# calendar-decoders.net
KiCad netlist of a schematic drawn in EAGLE
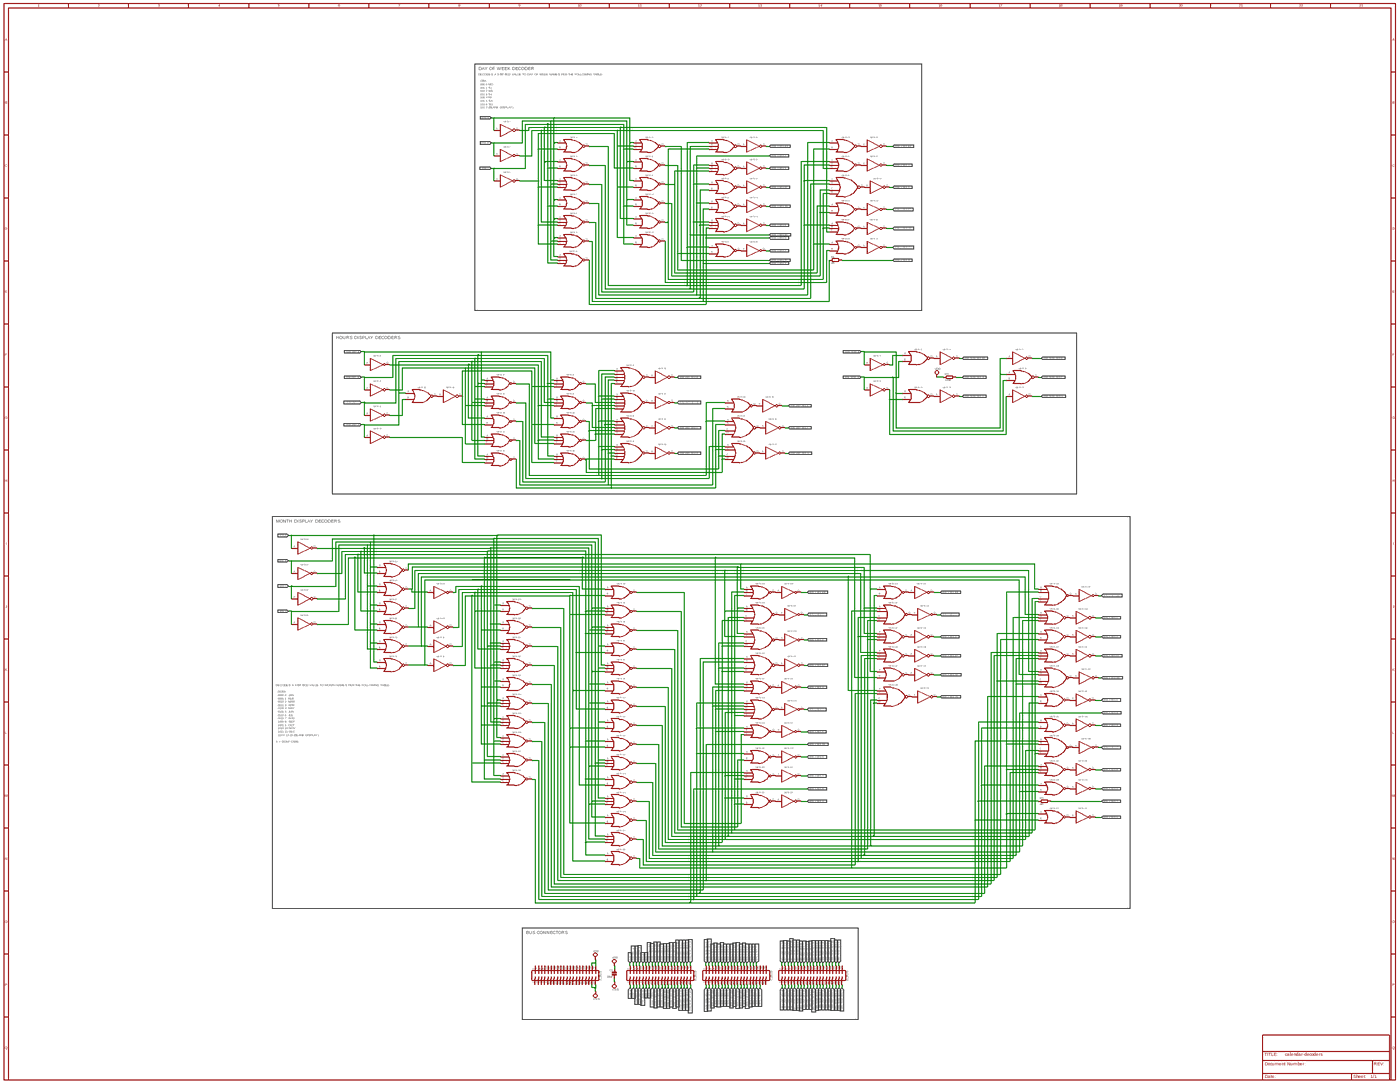
[diagram p0: schematic, sheet 1, overview]
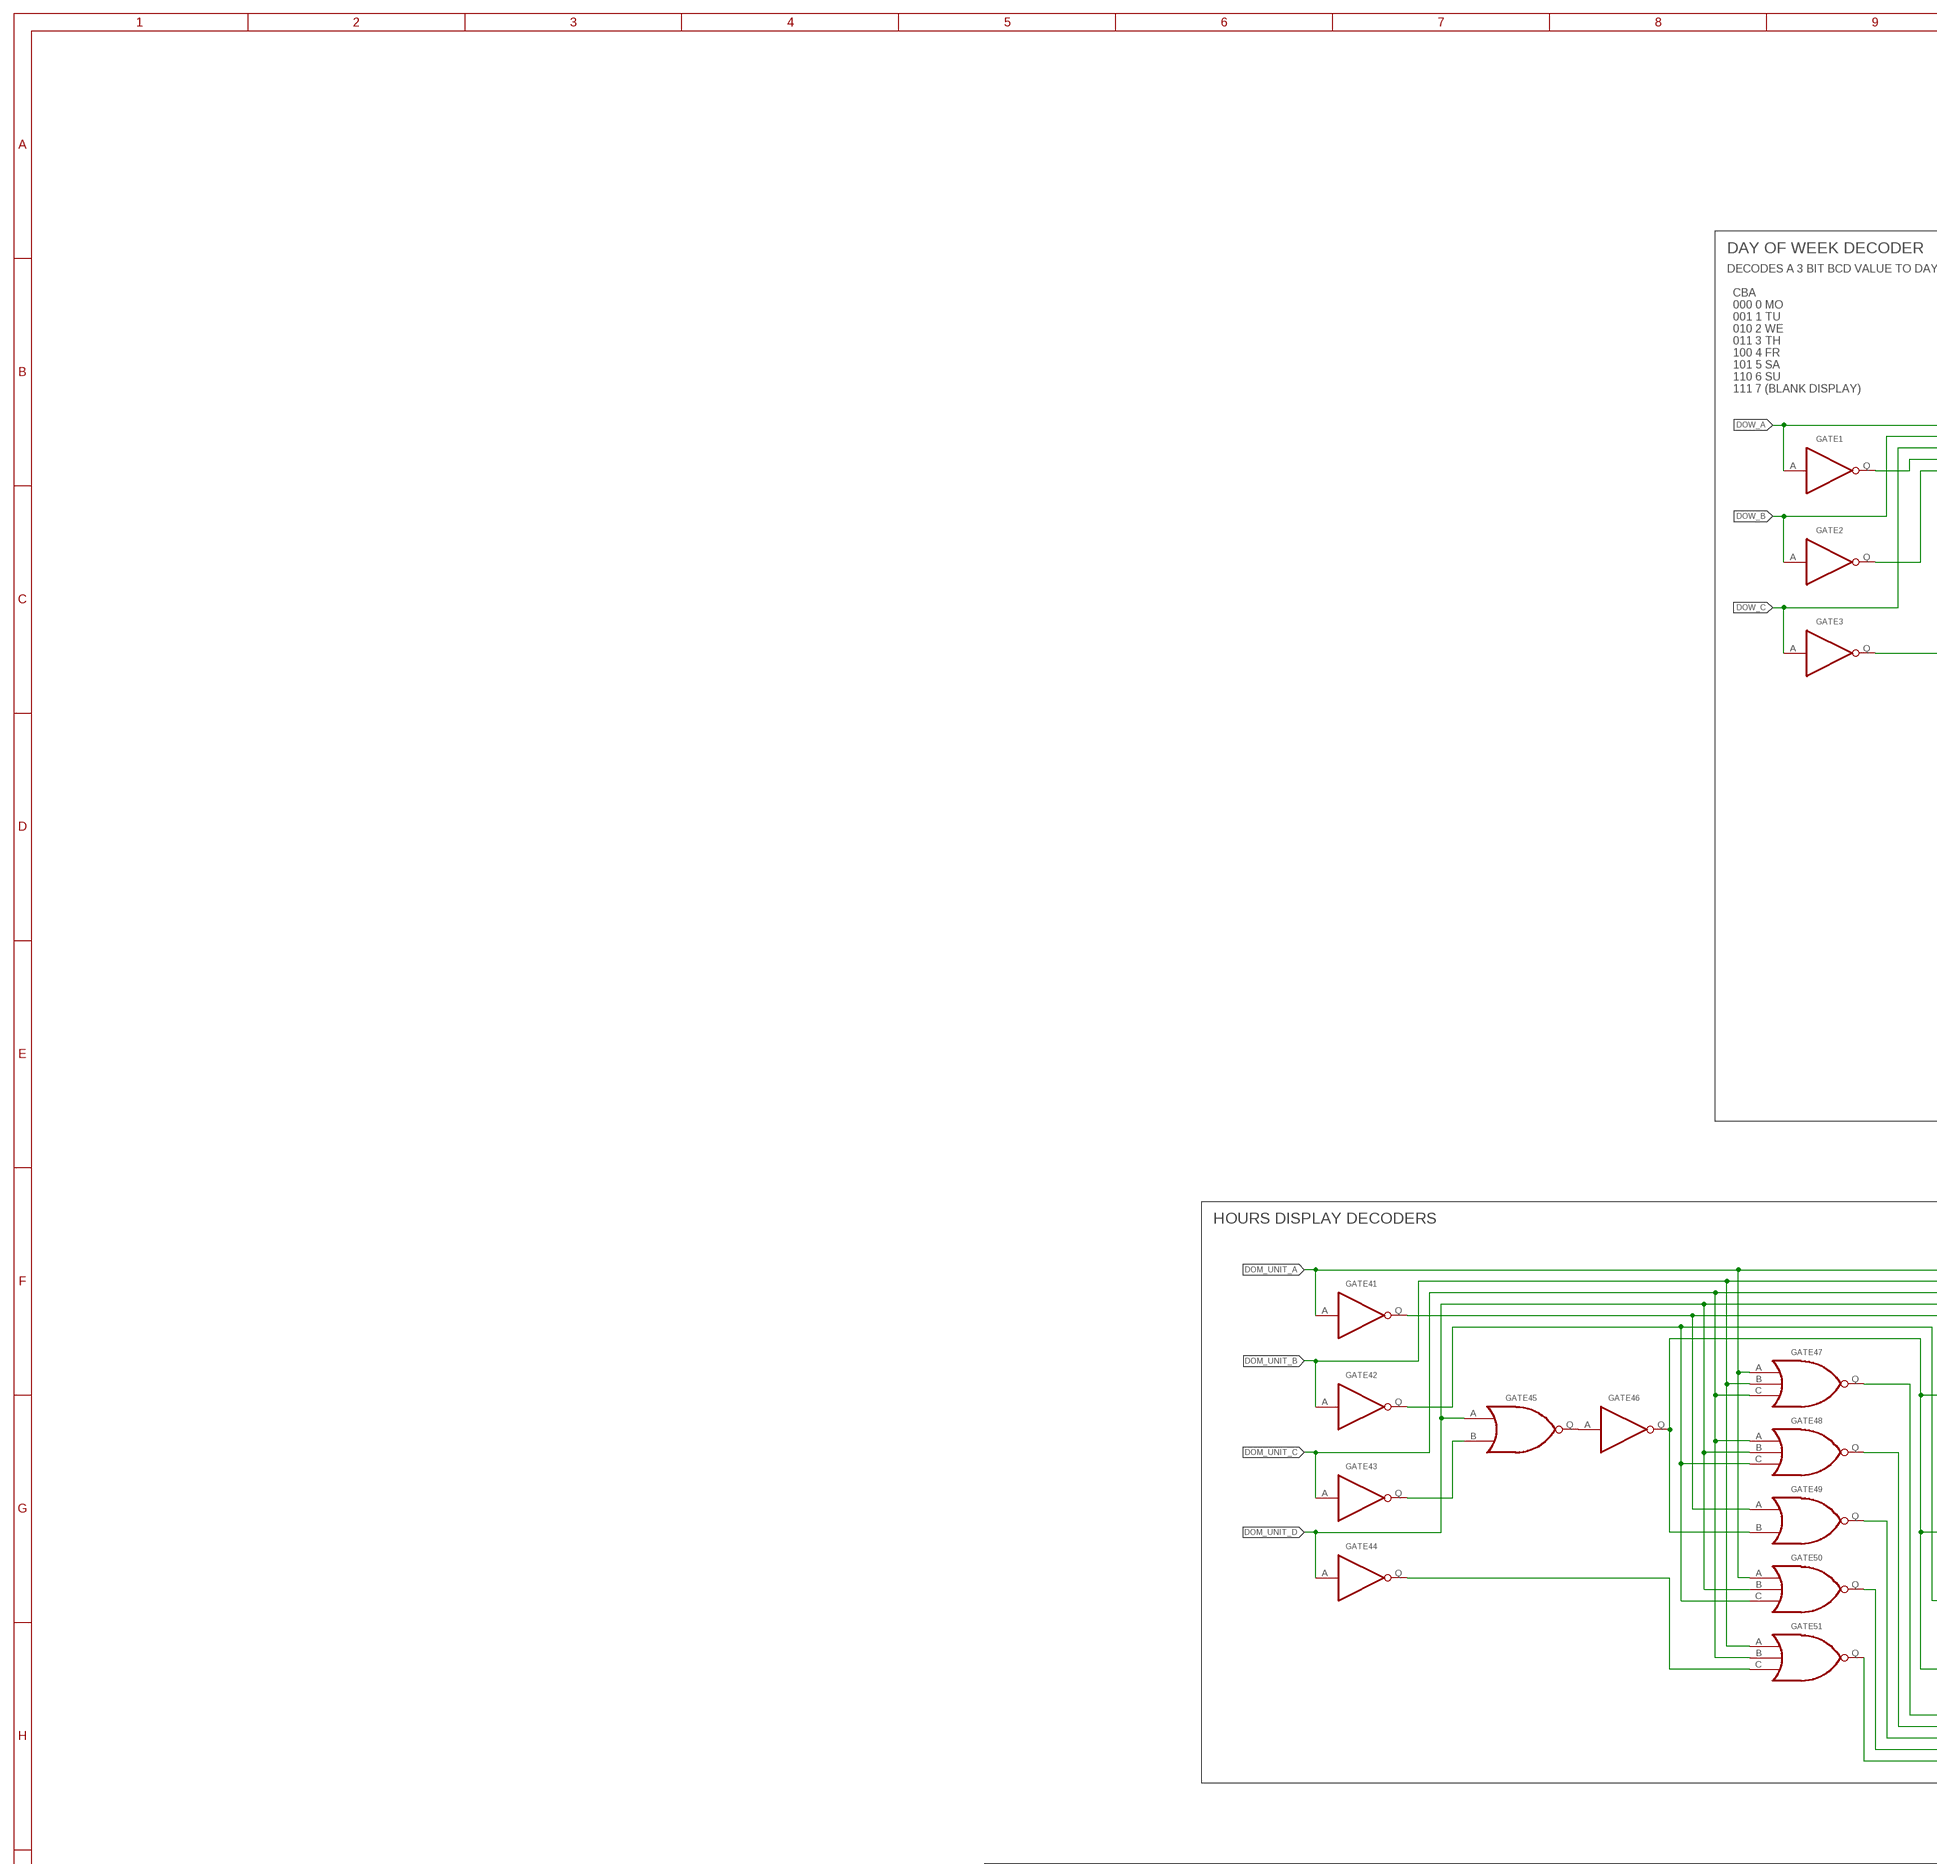
[diagram p1: schematic, sheet 1, part 1 of 6]
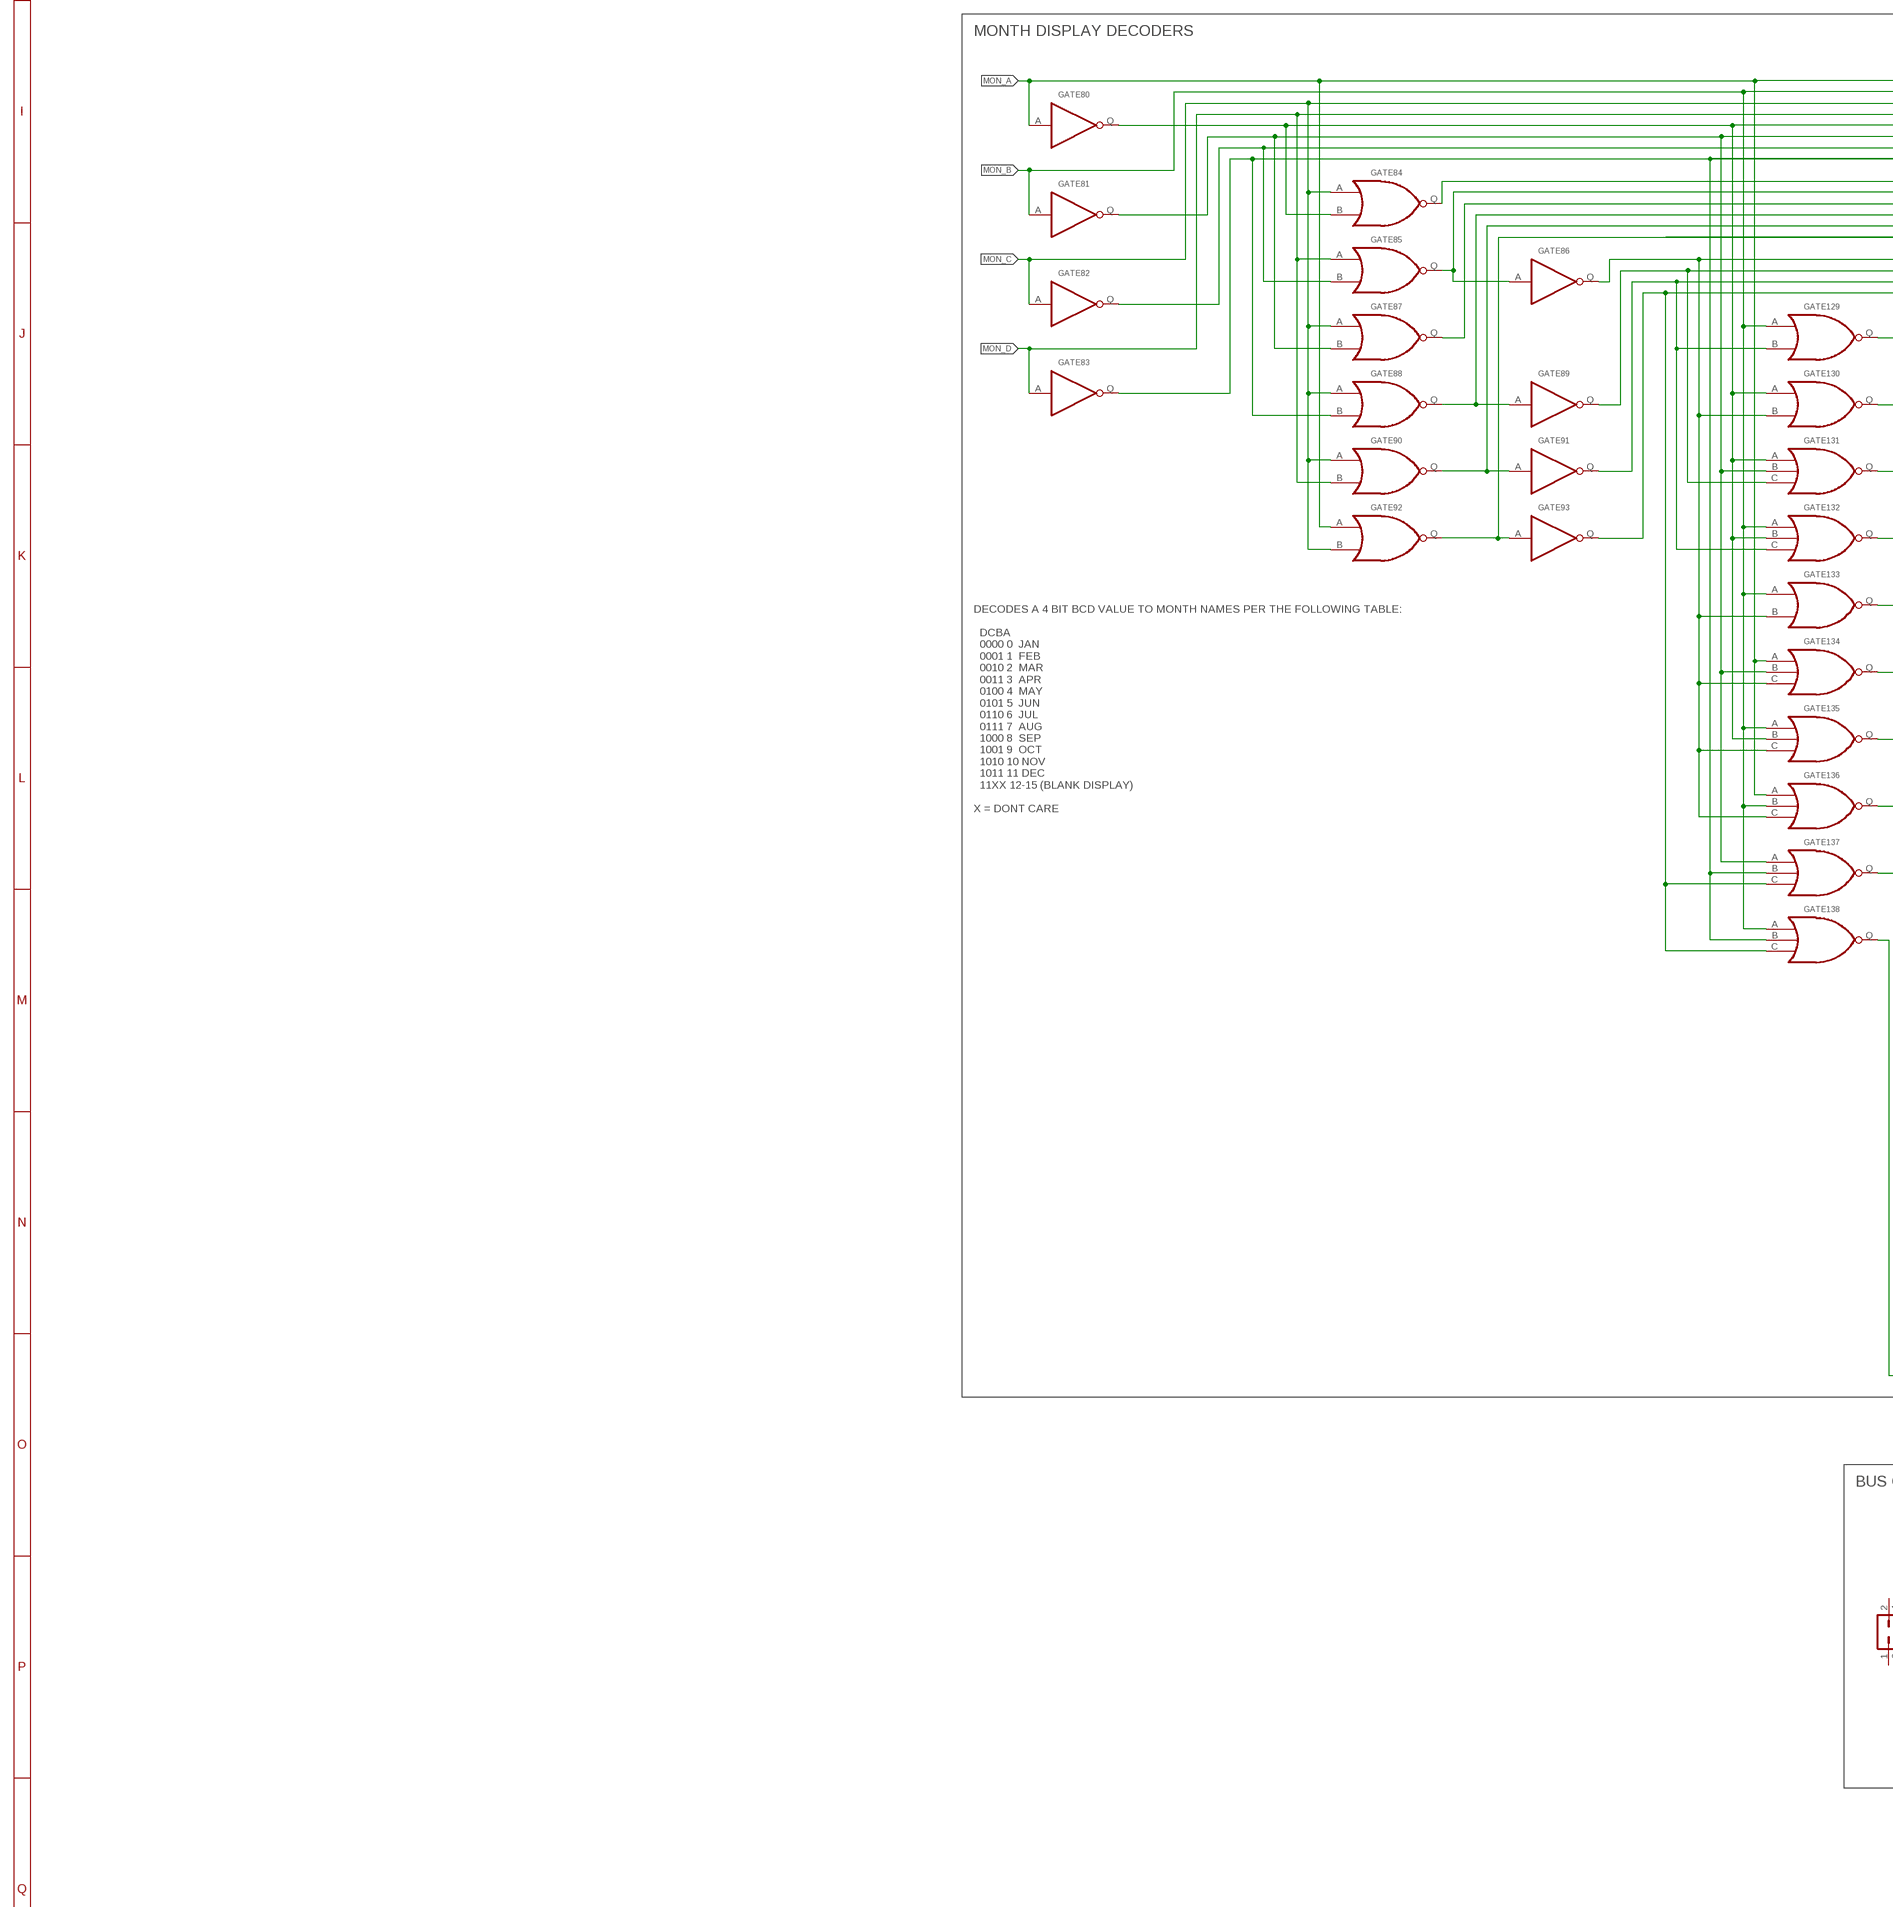
[diagram p2: schematic, sheet 1, part 2 of 6]
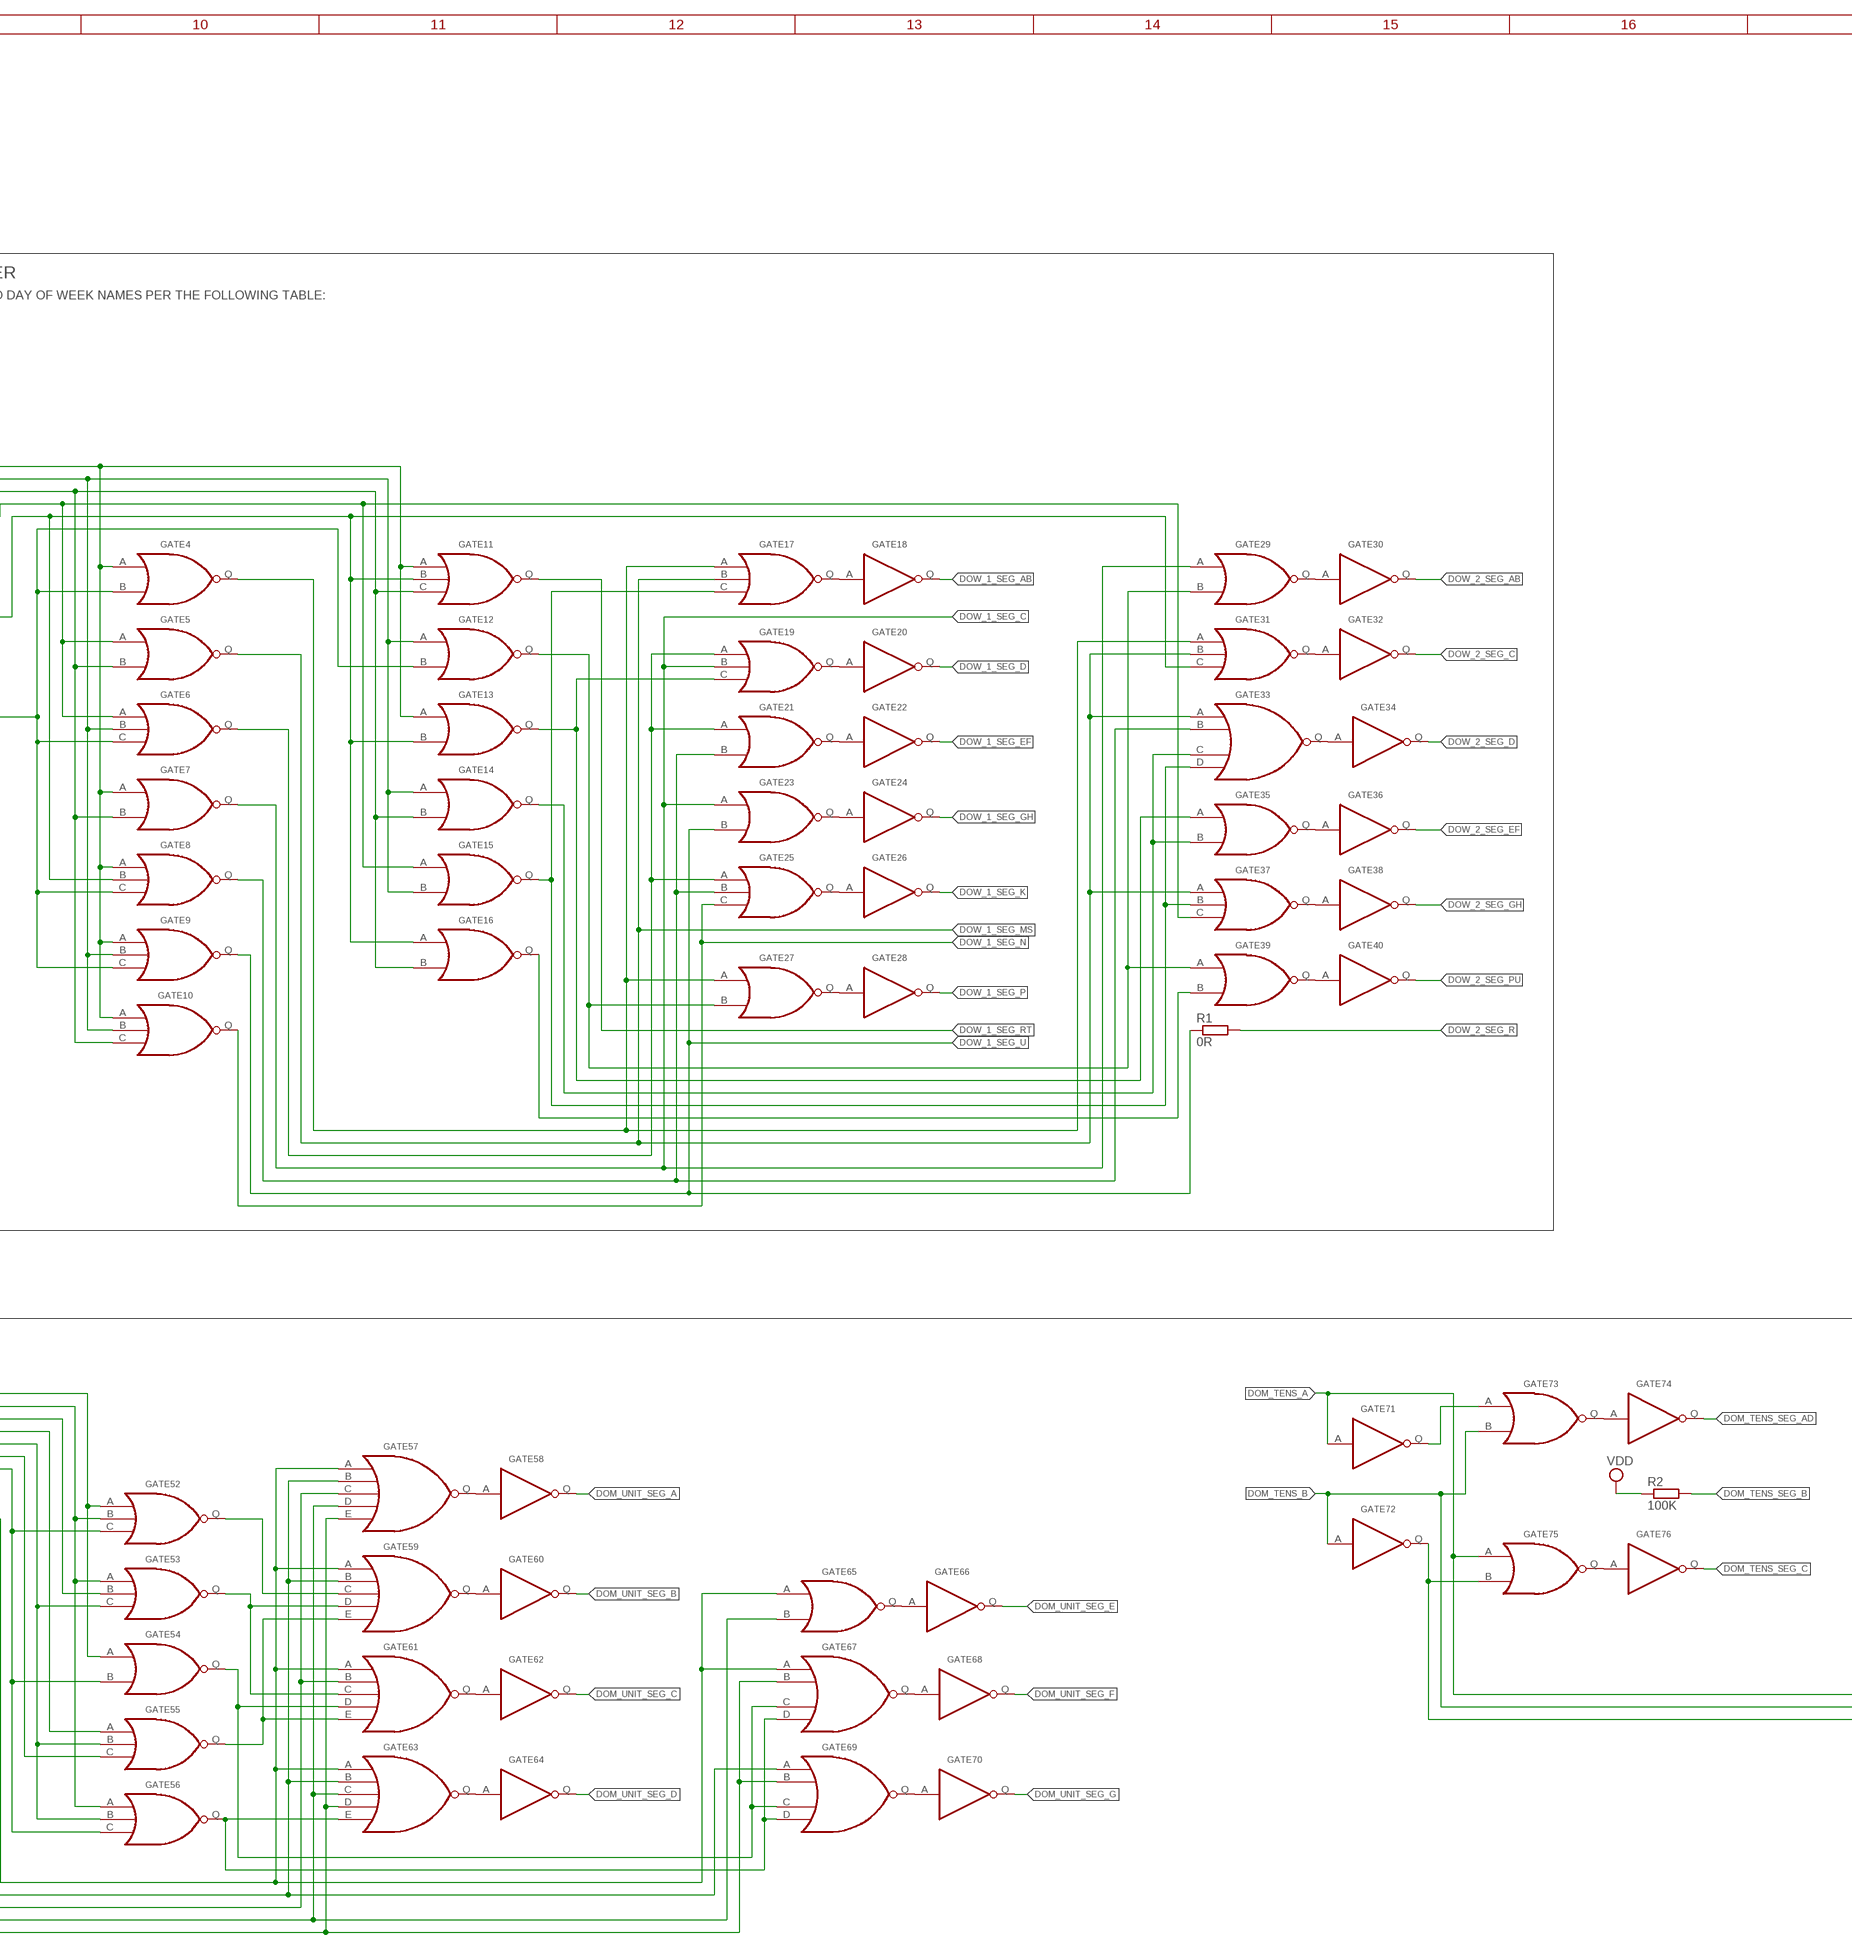
[diagram p3: schematic, sheet 1, part 3 of 6]
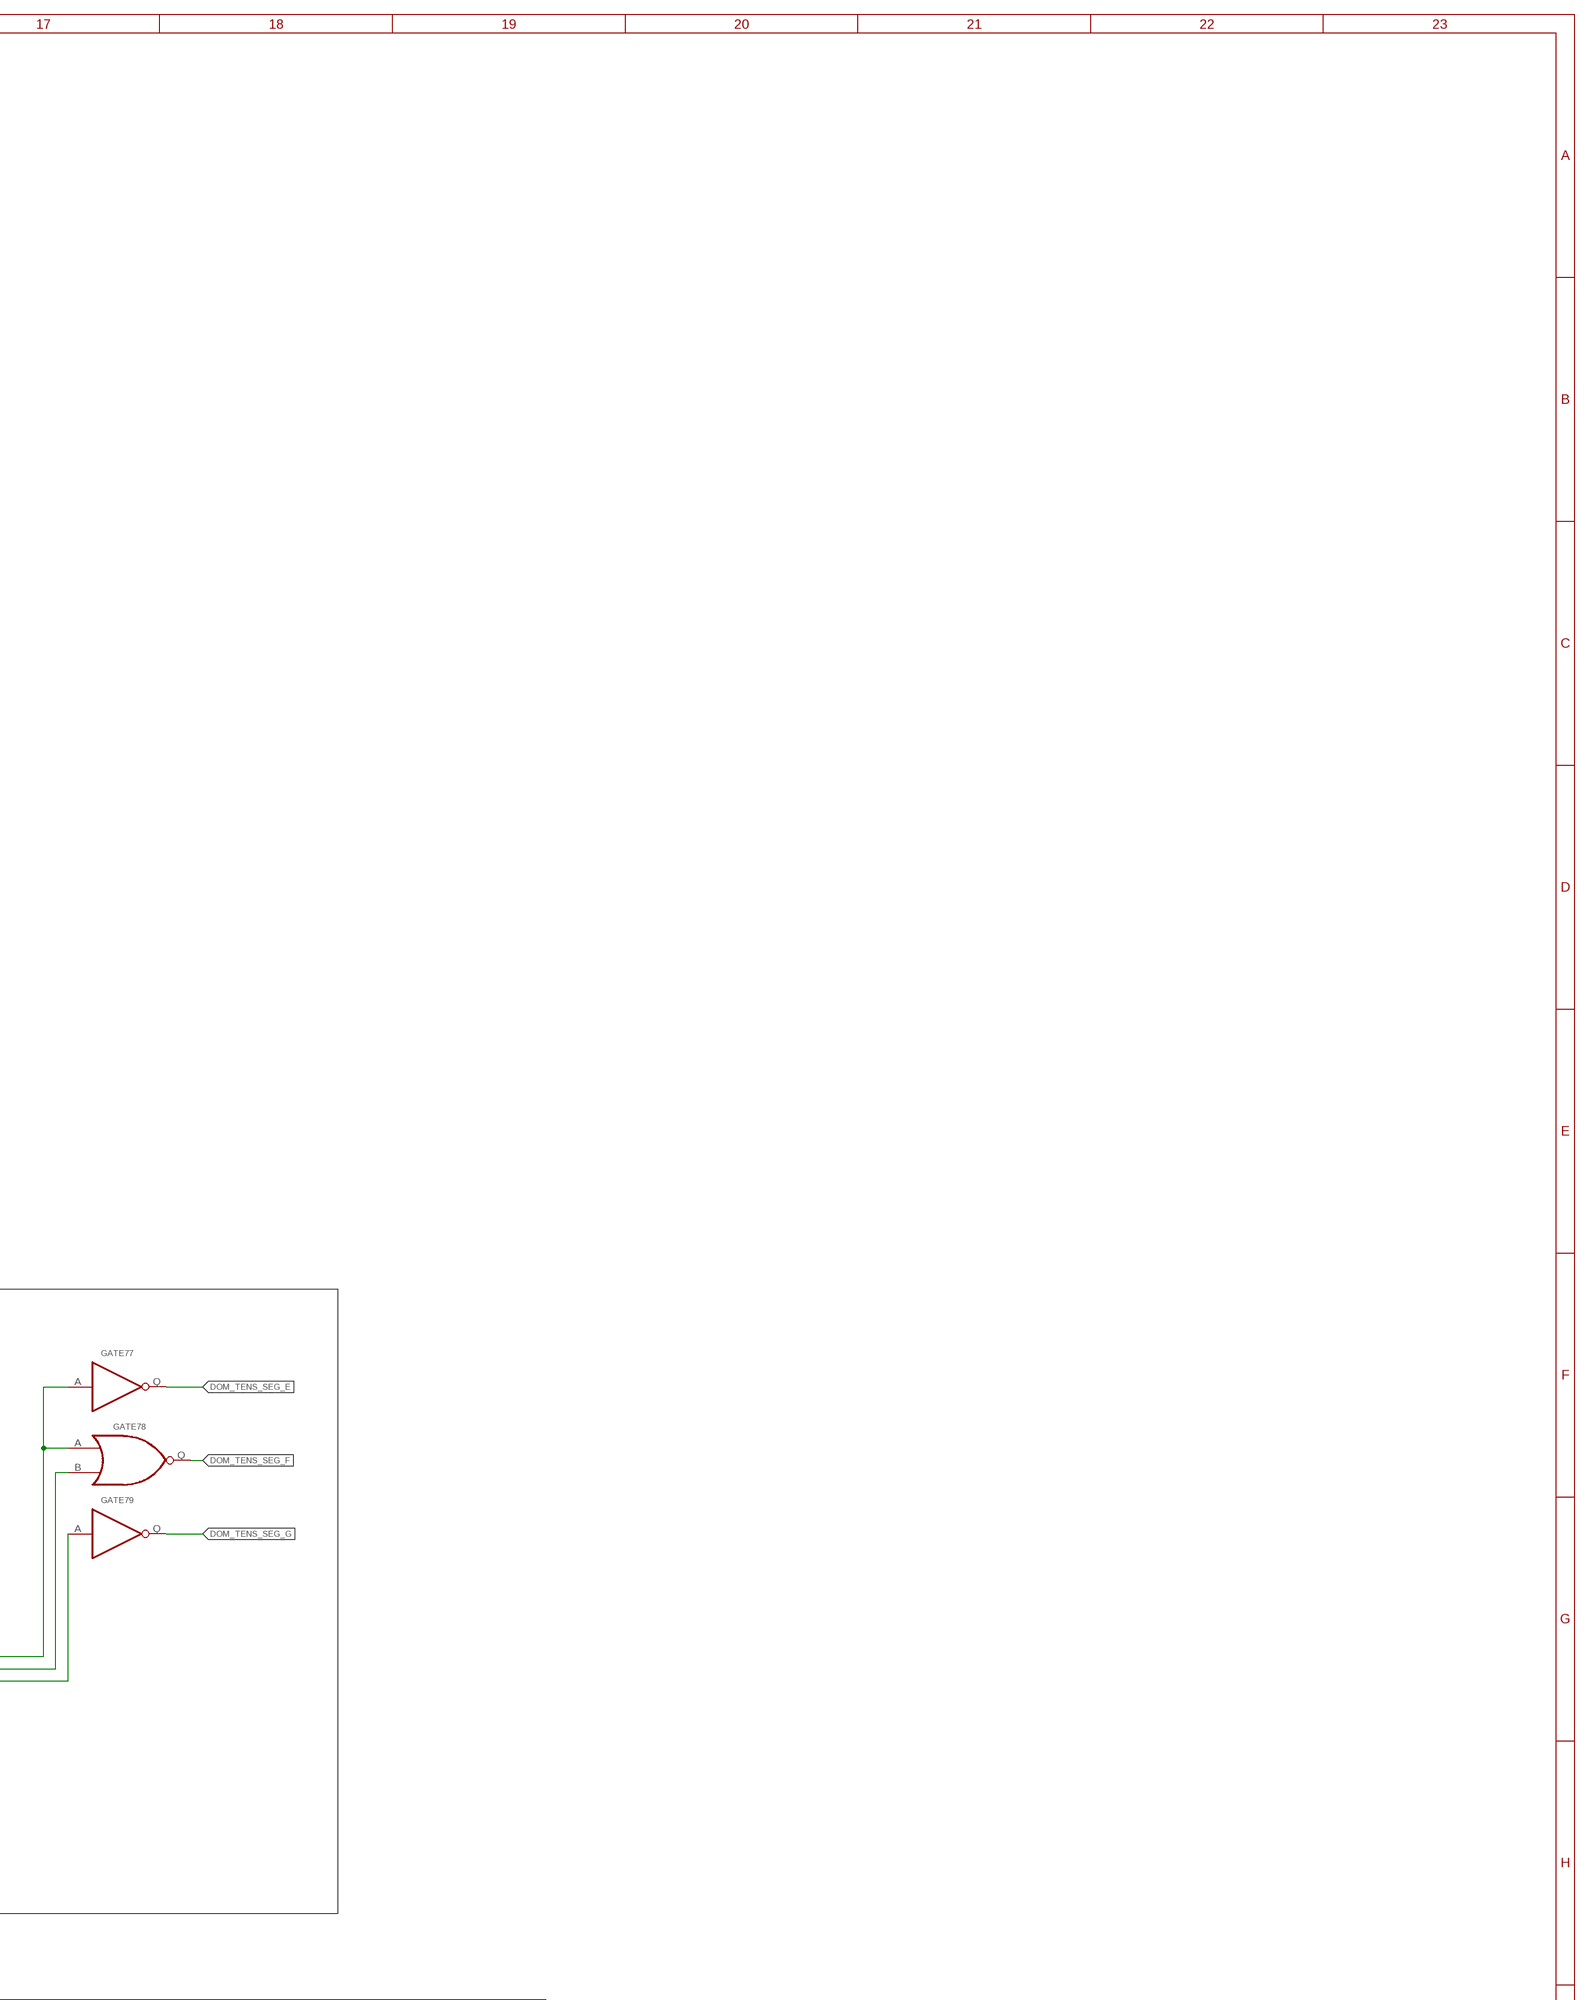
[diagram p4: schematic, sheet 1, part 4 of 6]
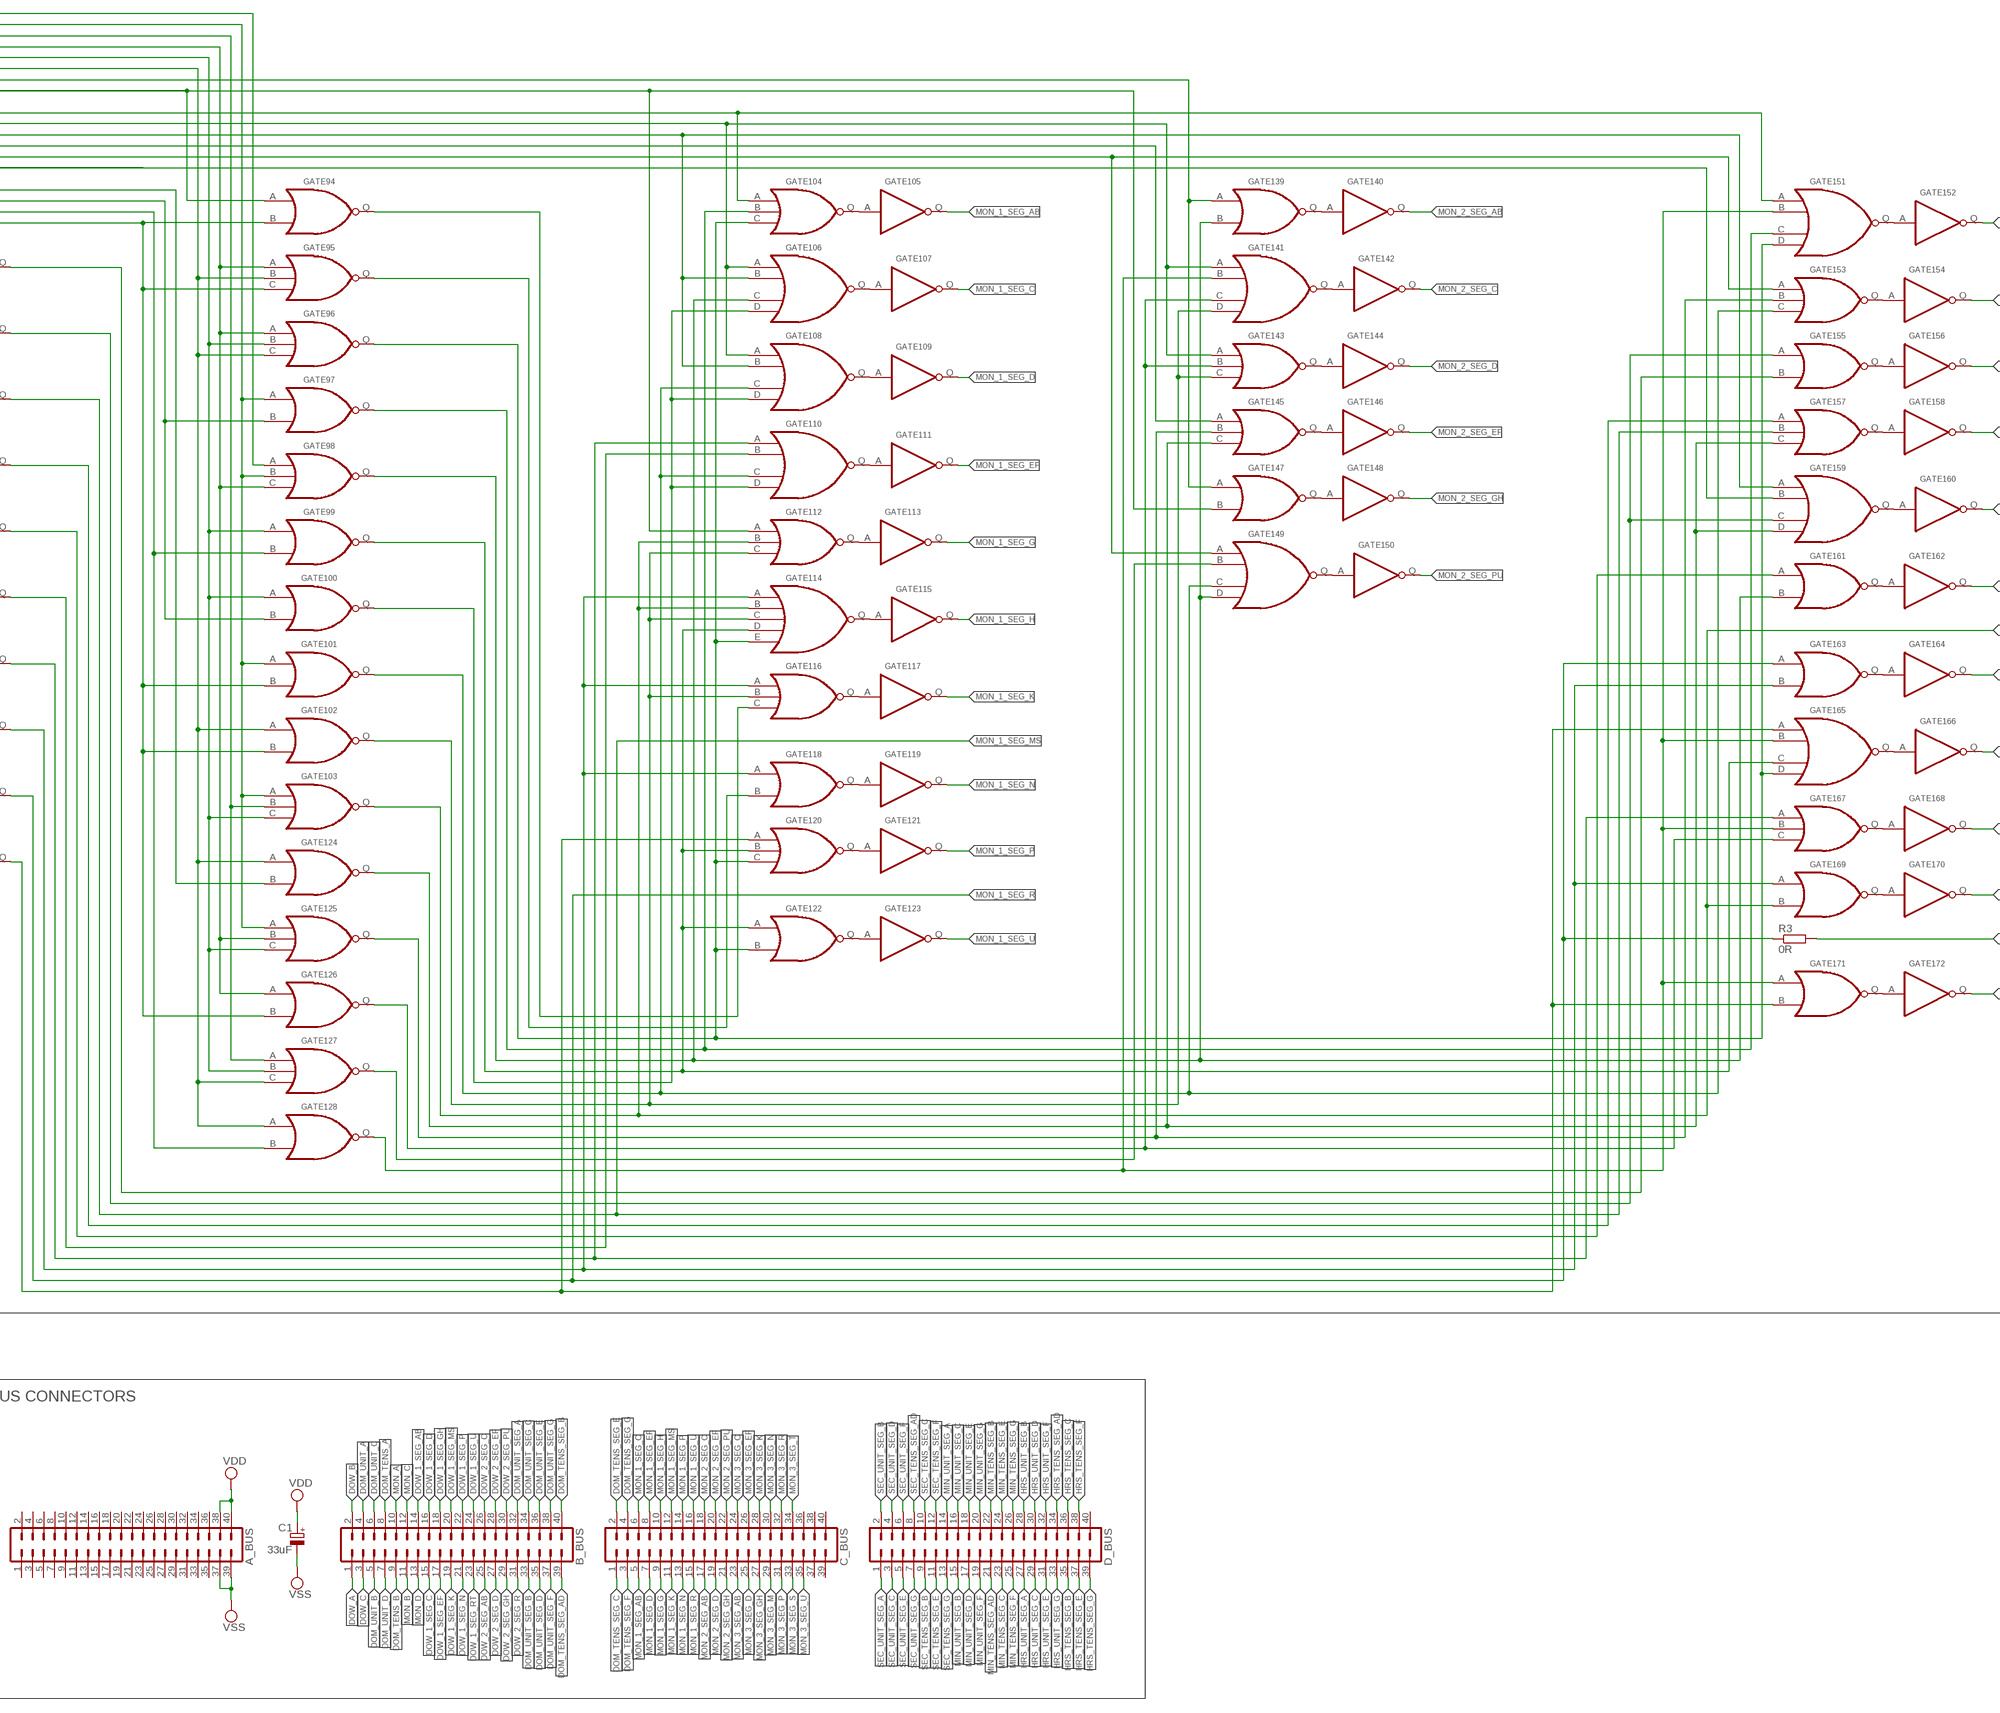
[diagram p5: schematic, sheet 1, part 5 of 6]
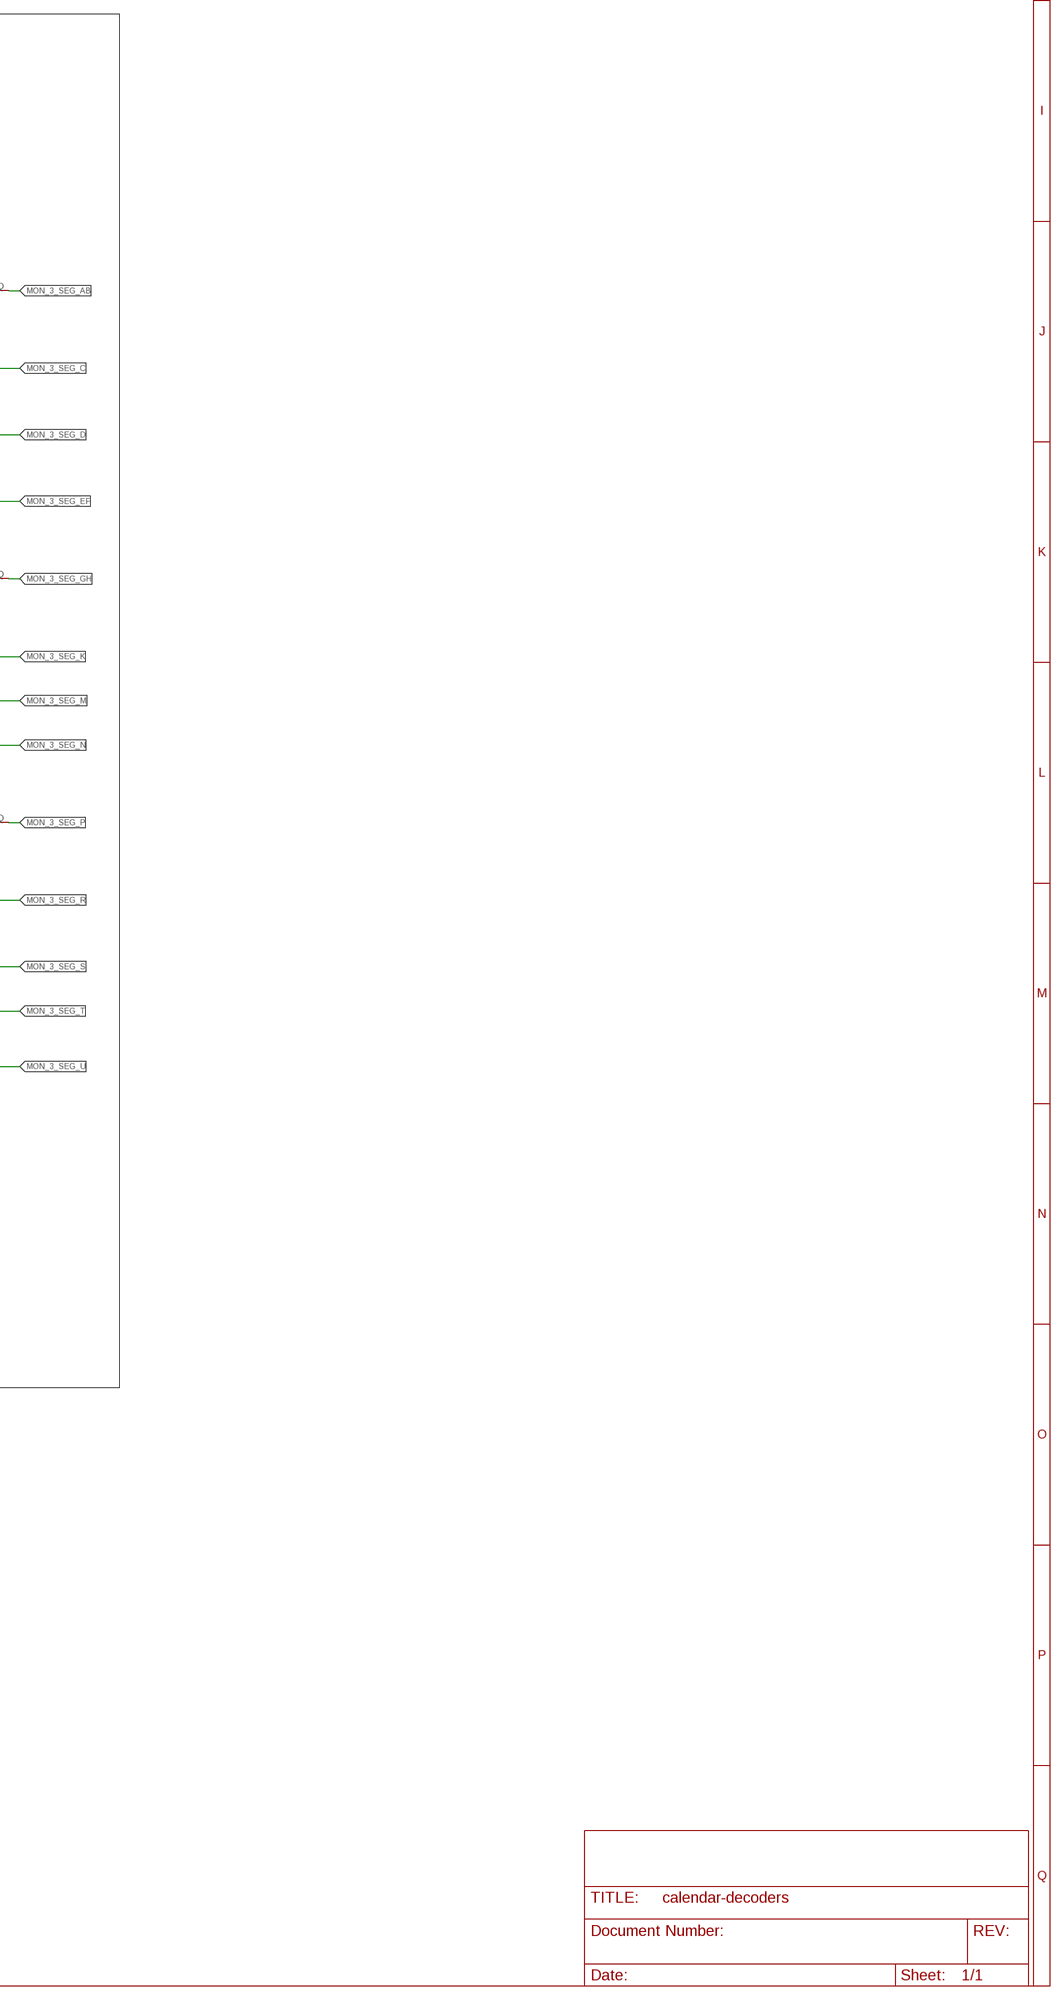
[diagram p6: schematic, sheet 1, part 6 of 6]

(export (version "E")
  (design (tool "Eeschema 10.0.6"))
  (components
    (comp (ref "A_BUS")
      (value "MA20-2")
      (footprint "eagle-import:MA20-2")
      (libsource (lib "eagle-import") (part "MA20-2"))
    )
    (comp (ref "B_BUS")
      (value "MA20-2")
      (footprint "eagle-import:MA20-2")
      (libsource (lib "eagle-import") (part "MA20-2"))
    )
    (comp (ref "C1")
      (value "33uF")
      (footprint "eagle-import:E2,5-6")
      (libsource (lib "eagle-import") (part "CPOL-EUE2.5-6"))
    )
    (comp (ref "C_BUS")
      (value "MA20-2")
      (footprint "eagle-import:MA20-2")
      (libsource (lib "eagle-import") (part "MA20-2"))
    )
    (comp (ref "D_BUS")
      (value "MA20-2")
      (footprint "eagle-import:MA20-2")
      (libsource (lib "eagle-import") (part "MA20-2"))
    )
    (comp (ref "GATE1")
      (value "INVERTER")
      (footprint "eagle-import:INVERTER")
      (libsource (lib "eagle-import") (part "INVERTER"))
    )
    (comp (ref "GATE2")
      (value "INVERTER")
      (footprint "eagle-import:INVERTER")
      (libsource (lib "eagle-import") (part "INVERTER"))
    )
    (comp (ref "GATE3")
      (value "INVERTER")
      (footprint "eagle-import:INVERTER")
      (libsource (lib "eagle-import") (part "INVERTER"))
    )
    (comp (ref "GATE4")
      (value "2NOR")
      (footprint "eagle-import:2NOR")
      (libsource (lib "eagle-import") (part "2NOR"))
    )
    (comp (ref "GATE5")
      (value "2NOR")
      (footprint "eagle-import:2NOR")
      (libsource (lib "eagle-import") (part "2NOR"))
    )
    (comp (ref "GATE6")
      (value "3NOR")
      (footprint "eagle-import:3NOR")
      (libsource (lib "eagle-import") (part "3NOR"))
    )
    (comp (ref "GATE7")
      (value "2NOR")
      (footprint "eagle-import:2NOR")
      (libsource (lib "eagle-import") (part "2NOR"))
    )
    (comp (ref "GATE8")
      (value "3NOR")
      (footprint "eagle-import:3NOR")
      (libsource (lib "eagle-import") (part "3NOR"))
    )
    (comp (ref "GATE9")
      (value "3NOR")
      (footprint "eagle-import:3NOR")
      (libsource (lib "eagle-import") (part "3NOR"))
    )
    (comp (ref "GATE10")
      (value "3NOR")
      (footprint "eagle-import:3NOR")
      (libsource (lib "eagle-import") (part "3NOR"))
    )
    (comp (ref "GATE11")
      (value "3NOR")
      (footprint "eagle-import:3NOR")
      (libsource (lib "eagle-import") (part "3NOR"))
    )
    (comp (ref "GATE12")
      (value "2NOR")
      (footprint "eagle-import:2NOR")
      (libsource (lib "eagle-import") (part "2NOR"))
    )
    (comp (ref "GATE13")
      (value "2NOR")
      (footprint "eagle-import:2NOR")
      (libsource (lib "eagle-import") (part "2NOR"))
    )
    (comp (ref "GATE14")
      (value "2NOR")
      (footprint "eagle-import:2NOR")
      (libsource (lib "eagle-import") (part "2NOR"))
    )
    (comp (ref "GATE15")
      (value "2NOR")
      (footprint "eagle-import:2NOR")
      (libsource (lib "eagle-import") (part "2NOR"))
    )
    (comp (ref "GATE16")
      (value "2NOR")
      (footprint "eagle-import:2NOR")
      (libsource (lib "eagle-import") (part "2NOR"))
    )
    (comp (ref "GATE17")
      (value "3NOR")
      (footprint "eagle-import:3NOR")
      (libsource (lib "eagle-import") (part "3NOR"))
    )
    (comp (ref "GATE18")
      (value "INVERTER")
      (footprint "eagle-import:INVERTER")
      (libsource (lib "eagle-import") (part "INVERTER"))
    )
    (comp (ref "GATE19")
      (value "3NOR")
      (footprint "eagle-import:3NOR")
      (libsource (lib "eagle-import") (part "3NOR"))
    )
    (comp (ref "GATE20")
      (value "INVERTER")
      (footprint "eagle-import:INVERTER")
      (libsource (lib "eagle-import") (part "INVERTER"))
    )
    (comp (ref "GATE21")
      (value "2NOR")
      (footprint "eagle-import:2NOR")
      (libsource (lib "eagle-import") (part "2NOR"))
    )
    (comp (ref "GATE22")
      (value "INVERTER")
      (footprint "eagle-import:INVERTER")
      (libsource (lib "eagle-import") (part "INVERTER"))
    )
    (comp (ref "GATE23")
      (value "2NOR")
      (footprint "eagle-import:2NOR")
      (libsource (lib "eagle-import") (part "2NOR"))
    )
    (comp (ref "GATE24")
      (value "INVERTER")
      (footprint "eagle-import:INVERTER")
      (libsource (lib "eagle-import") (part "INVERTER"))
    )
    (comp (ref "GATE25")
      (value "3NOR")
      (footprint "eagle-import:3NOR")
      (libsource (lib "eagle-import") (part "3NOR"))
    )
    (comp (ref "GATE26")
      (value "INVERTER")
      (footprint "eagle-import:INVERTER")
      (libsource (lib "eagle-import") (part "INVERTER"))
    )
    (comp (ref "GATE27")
      (value "2NOR")
      (footprint "eagle-import:2NOR")
      (libsource (lib "eagle-import") (part "2NOR"))
    )
    (comp (ref "GATE28")
      (value "INVERTER")
      (footprint "eagle-import:INVERTER")
      (libsource (lib "eagle-import") (part "INVERTER"))
    )
    (comp (ref "GATE29")
      (value "2NOR")
      (footprint "eagle-import:2NOR")
      (libsource (lib "eagle-import") (part "2NOR"))
    )
    (comp (ref "GATE30")
      (value "INVERTER")
      (footprint "eagle-import:INVERTER")
      (libsource (lib "eagle-import") (part "INVERTER"))
    )
    (comp (ref "GATE31")
      (value "3NOR")
      (footprint "eagle-import:3NOR")
      (libsource (lib "eagle-import") (part "3NOR"))
    )
    (comp (ref "GATE32")
      (value "INVERTER")
      (footprint "eagle-import:INVERTER")
      (libsource (lib "eagle-import") (part "INVERTER"))
    )
    (comp (ref "GATE33")
      (value "4NOR")
      (footprint "eagle-import:4NOR")
      (libsource (lib "eagle-import") (part "4NOR"))
    )
    (comp (ref "GATE34")
      (value "INVERTER")
      (footprint "eagle-import:INVERTER")
      (libsource (lib "eagle-import") (part "INVERTER"))
    )
    (comp (ref "GATE35")
      (value "2NOR")
      (footprint "eagle-import:2NOR")
      (libsource (lib "eagle-import") (part "2NOR"))
    )
    (comp (ref "GATE36")
      (value "INVERTER")
      (footprint "eagle-import:INVERTER")
      (libsource (lib "eagle-import") (part "INVERTER"))
    )
    (comp (ref "GATE37")
      (value "3NOR")
      (footprint "eagle-import:3NOR")
      (libsource (lib "eagle-import") (part "3NOR"))
    )
    (comp (ref "GATE38")
      (value "INVERTER")
      (footprint "eagle-import:INVERTER")
      (libsource (lib "eagle-import") (part "INVERTER"))
    )
    (comp (ref "GATE39")
      (value "2NOR")
      (footprint "eagle-import:2NOR")
      (libsource (lib "eagle-import") (part "2NOR"))
    )
    (comp (ref "GATE40")
      (value "INVERTER")
      (footprint "eagle-import:INVERTER")
      (libsource (lib "eagle-import") (part "INVERTER"))
    )
    (comp (ref "GATE41")
      (value "INVERTER")
      (footprint "eagle-import:INVERTER")
      (libsource (lib "eagle-import") (part "INVERTER"))
    )
    (comp (ref "GATE42")
      (value "INVERTER")
      (footprint "eagle-import:INVERTER")
      (libsource (lib "eagle-import") (part "INVERTER"))
    )
    (comp (ref "GATE43")
      (value "INVERTER")
      (footprint "eagle-import:INVERTER")
      (libsource (lib "eagle-import") (part "INVERTER"))
    )
    (comp (ref "GATE44")
      (value "INVERTER")
      (footprint "eagle-import:INVERTER")
      (libsource (lib "eagle-import") (part "INVERTER"))
    )
    (comp (ref "GATE45")
      (value "2NOR")
      (footprint "eagle-import:2NOR")
      (libsource (lib "eagle-import") (part "2NOR"))
    )
    (comp (ref "GATE46")
      (value "INVERTER")
      (footprint "eagle-import:INVERTER")
      (libsource (lib "eagle-import") (part "INVERTER"))
    )
    (comp (ref "GATE47")
      (value "3NOR")
      (footprint "eagle-import:3NOR")
      (libsource (lib "eagle-import") (part "3NOR"))
    )
    (comp (ref "GATE48")
      (value "3NOR")
      (footprint "eagle-import:3NOR")
      (libsource (lib "eagle-import") (part "3NOR"))
    )
    (comp (ref "GATE49")
      (value "2NOR")
      (footprint "eagle-import:2NOR")
      (libsource (lib "eagle-import") (part "2NOR"))
    )
    (comp (ref "GATE50")
      (value "3NOR")
      (footprint "eagle-import:3NOR")
      (libsource (lib "eagle-import") (part "3NOR"))
    )
    (comp (ref "GATE51")
      (value "3NOR")
      (footprint "eagle-import:3NOR")
      (libsource (lib "eagle-import") (part "3NOR"))
    )
    (comp (ref "GATE52")
      (value "3NOR")
      (footprint "eagle-import:3NOR")
      (libsource (lib "eagle-import") (part "3NOR"))
    )
    (comp (ref "GATE53")
      (value "3NOR")
      (footprint "eagle-import:3NOR")
      (libsource (lib "eagle-import") (part "3NOR"))
    )
    (comp (ref "GATE54")
      (value "2NOR")
      (footprint "eagle-import:2NOR")
      (libsource (lib "eagle-import") (part "2NOR"))
    )
    (comp (ref "GATE55")
      (value "3NOR")
      (footprint "eagle-import:3NOR")
      (libsource (lib "eagle-import") (part "3NOR"))
    )
    (comp (ref "GATE56")
      (value "3NOR")
      (footprint "eagle-import:3NOR")
      (libsource (lib "eagle-import") (part "3NOR"))
    )
    (comp (ref "GATE57")
      (value "5NOR")
      (footprint "eagle-import:5NOR")
      (libsource (lib "eagle-import") (part "5NOR"))
    )
    (comp (ref "GATE58")
      (value "INVERTER")
      (footprint "eagle-import:INVERTER")
      (libsource (lib "eagle-import") (part "INVERTER"))
    )
    (comp (ref "GATE59")
      (value "5NOR")
      (footprint "eagle-import:5NOR")
      (libsource (lib "eagle-import") (part "5NOR"))
    )
    (comp (ref "GATE60")
      (value "INVERTER")
      (footprint "eagle-import:INVERTER")
      (libsource (lib "eagle-import") (part "INVERTER"))
    )
    (comp (ref "GATE61")
      (value "5NOR")
      (footprint "eagle-import:5NOR")
      (libsource (lib "eagle-import") (part "5NOR"))
    )
    (comp (ref "GATE62")
      (value "INVERTER")
      (footprint "eagle-import:INVERTER")
      (libsource (lib "eagle-import") (part "INVERTER"))
    )
    (comp (ref "GATE63")
      (value "5NOR")
      (footprint "eagle-import:5NOR")
      (libsource (lib "eagle-import") (part "5NOR"))
    )
    (comp (ref "GATE64")
      (value "INVERTER")
      (footprint "eagle-import:INVERTER")
      (libsource (lib "eagle-import") (part "INVERTER"))
    )
    (comp (ref "GATE65")
      (value "2NOR")
      (footprint "eagle-import:2NOR")
      (libsource (lib "eagle-import") (part "2NOR"))
    )
    (comp (ref "GATE66")
      (value "INVERTER")
      (footprint "eagle-import:INVERTER")
      (libsource (lib "eagle-import") (part "INVERTER"))
    )
    (comp (ref "GATE67")
      (value "4NOR")
      (footprint "eagle-import:4NOR")
      (libsource (lib "eagle-import") (part "4NOR"))
    )
    (comp (ref "GATE68")
      (value "INVERTER")
      (footprint "eagle-import:INVERTER")
      (libsource (lib "eagle-import") (part "INVERTER"))
    )
    (comp (ref "GATE69")
      (value "4NOR")
      (footprint "eagle-import:4NOR")
      (libsource (lib "eagle-import") (part "4NOR"))
    )
    (comp (ref "GATE70")
      (value "INVERTER")
      (footprint "eagle-import:INVERTER")
      (libsource (lib "eagle-import") (part "INVERTER"))
    )
    (comp (ref "GATE71")
      (value "INVERTER")
      (footprint "eagle-import:INVERTER")
      (libsource (lib "eagle-import") (part "INVERTER"))
    )
    (comp (ref "GATE72")
      (value "INVERTER")
      (footprint "eagle-import:INVERTER")
      (libsource (lib "eagle-import") (part "INVERTER"))
    )
    (comp (ref "GATE73")
      (value "2NOR")
      (footprint "eagle-import:2NOR")
      (libsource (lib "eagle-import") (part "2NOR"))
    )
    (comp (ref "GATE74")
      (value "INVERTER")
      (footprint "eagle-import:INVERTER")
      (libsource (lib "eagle-import") (part "INVERTER"))
    )
    (comp (ref "GATE75")
      (value "2NOR")
      (footprint "eagle-import:2NOR")
      (libsource (lib "eagle-import") (part "2NOR"))
    )
    (comp (ref "GATE76")
      (value "INVERTER")
      (footprint "eagle-import:INVERTER")
      (libsource (lib "eagle-import") (part "INVERTER"))
    )
    (comp (ref "GATE77")
      (value "INVERTER")
      (footprint "eagle-import:INVERTER")
      (libsource (lib "eagle-import") (part "INVERTER"))
    )
    (comp (ref "GATE78")
      (value "2NOR")
      (footprint "eagle-import:2NOR")
      (libsource (lib "eagle-import") (part "2NOR"))
    )
    (comp (ref "GATE79")
      (value "INVERTER")
      (footprint "eagle-import:INVERTER")
      (libsource (lib "eagle-import") (part "INVERTER"))
    )
    (comp (ref "GATE80")
      (value "INVERTER")
      (footprint "eagle-import:INVERTER")
      (libsource (lib "eagle-import") (part "INVERTER"))
    )
    (comp (ref "GATE81")
      (value "INVERTER")
      (footprint "eagle-import:INVERTER")
      (libsource (lib "eagle-import") (part "INVERTER"))
    )
    (comp (ref "GATE82")
      (value "INVERTER")
      (footprint "eagle-import:INVERTER")
      (libsource (lib "eagle-import") (part "INVERTER"))
    )
    (comp (ref "GATE83")
      (value "INVERTER")
      (footprint "eagle-import:INVERTER")
      (libsource (lib "eagle-import") (part "INVERTER"))
    )
    (comp (ref "GATE84")
      (value "2NOR")
      (footprint "eagle-import:2NOR")
      (libsource (lib "eagle-import") (part "2NOR"))
    )
    (comp (ref "GATE85")
      (value "2NOR")
      (footprint "eagle-import:2NOR")
      (libsource (lib "eagle-import") (part "2NOR"))
    )
    (comp (ref "GATE86")
      (value "INVERTER")
      (footprint "eagle-import:INVERTER")
      (libsource (lib "eagle-import") (part "INVERTER"))
    )
    (comp (ref "GATE87")
      (value "2NOR")
      (footprint "eagle-import:2NOR")
      (libsource (lib "eagle-import") (part "2NOR"))
    )
    (comp (ref "GATE88")
      (value "2NOR")
      (footprint "eagle-import:2NOR")
      (libsource (lib "eagle-import") (part "2NOR"))
    )
    (comp (ref "GATE89")
      (value "INVERTER")
      (footprint "eagle-import:INVERTER")
      (libsource (lib "eagle-import") (part "INVERTER"))
    )
    (comp (ref "GATE90")
      (value "2NOR")
      (footprint "eagle-import:2NOR")
      (libsource (lib "eagle-import") (part "2NOR"))
    )
    (comp (ref "GATE91")
      (value "INVERTER")
      (footprint "eagle-import:INVERTER")
      (libsource (lib "eagle-import") (part "INVERTER"))
    )
    (comp (ref "GATE92")
      (value "2NOR")
      (footprint "eagle-import:2NOR")
      (libsource (lib "eagle-import") (part "2NOR"))
    )
    (comp (ref "GATE93")
      (value "INVERTER")
      (footprint "eagle-import:INVERTER")
      (libsource (lib "eagle-import") (part "INVERTER"))
    )
    (comp (ref "GATE94")
      (value "2NOR")
      (footprint "eagle-import:2NOR")
      (libsource (lib "eagle-import") (part "2NOR"))
    )
    (comp (ref "GATE95")
      (value "3NOR")
      (footprint "eagle-import:3NOR")
      (libsource (lib "eagle-import") (part "3NOR"))
    )
    (comp (ref "GATE96")
      (value "3NOR")
      (footprint "eagle-import:3NOR")
      (libsource (lib "eagle-import") (part "3NOR"))
    )
    (comp (ref "GATE97")
      (value "2NOR")
      (footprint "eagle-import:2NOR")
      (libsource (lib "eagle-import") (part "2NOR"))
    )
    (comp (ref "GATE98")
      (value "3NOR")
      (footprint "eagle-import:3NOR")
      (libsource (lib "eagle-import") (part "3NOR"))
    )
    (comp (ref "GATE99")
      (value "2NOR")
      (footprint "eagle-import:2NOR")
      (libsource (lib "eagle-import") (part "2NOR"))
    )
    (comp (ref "GATE100")
      (value "2NOR")
      (footprint "eagle-import:2NOR")
      (libsource (lib "eagle-import") (part "2NOR"))
    )
    (comp (ref "GATE101")
      (value "2NOR")
      (footprint "eagle-import:2NOR")
      (libsource (lib "eagle-import") (part "2NOR"))
    )
    (comp (ref "GATE102")
      (value "2NOR")
      (footprint "eagle-import:2NOR")
      (libsource (lib "eagle-import") (part "2NOR"))
    )
    (comp (ref "GATE103")
      (value "3NOR")
      (footprint "eagle-import:3NOR")
      (libsource (lib "eagle-import") (part "3NOR"))
    )
    (comp (ref "GATE104")
      (value "3NOR")
      (footprint "eagle-import:3NOR")
      (libsource (lib "eagle-import") (part "3NOR"))
    )
    (comp (ref "GATE105")
      (value "INVERTER")
      (footprint "eagle-import:INVERTER")
      (libsource (lib "eagle-import") (part "INVERTER"))
    )
    (comp (ref "GATE106")
      (value "4NOR")
      (footprint "eagle-import:4NOR")
      (libsource (lib "eagle-import") (part "4NOR"))
    )
    (comp (ref "GATE107")
      (value "INVERTER")
      (footprint "eagle-import:INVERTER")
      (libsource (lib "eagle-import") (part "INVERTER"))
    )
    (comp (ref "GATE108")
      (value "4NOR")
      (footprint "eagle-import:4NOR")
      (libsource (lib "eagle-import") (part "4NOR"))
    )
    (comp (ref "GATE109")
      (value "INVERTER")
      (footprint "eagle-import:INVERTER")
      (libsource (lib "eagle-import") (part "INVERTER"))
    )
    (comp (ref "GATE110")
      (value "4NOR")
      (footprint "eagle-import:4NOR")
      (libsource (lib "eagle-import") (part "4NOR"))
    )
    (comp (ref "GATE111")
      (value "INVERTER")
      (footprint "eagle-import:INVERTER")
      (libsource (lib "eagle-import") (part "INVERTER"))
    )
    (comp (ref "GATE112")
      (value "3NOR")
      (footprint "eagle-import:3NOR")
      (libsource (lib "eagle-import") (part "3NOR"))
    )
    (comp (ref "GATE113")
      (value "INVERTER")
      (footprint "eagle-import:INVERTER")
      (libsource (lib "eagle-import") (part "INVERTER"))
    )
    (comp (ref "GATE114")
      (value "5NOR")
      (footprint "eagle-import:5NOR")
      (libsource (lib "eagle-import") (part "5NOR"))
    )
    (comp (ref "GATE115")
      (value "INVERTER")
      (footprint "eagle-import:INVERTER")
      (libsource (lib "eagle-import") (part "INVERTER"))
    )
    (comp (ref "GATE116")
      (value "3NOR")
      (footprint "eagle-import:3NOR")
      (libsource (lib "eagle-import") (part "3NOR"))
    )
    (comp (ref "GATE117")
      (value "INVERTER")
      (footprint "eagle-import:INVERTER")
      (libsource (lib "eagle-import") (part "INVERTER"))
    )
    (comp (ref "GATE118")
      (value "2NOR")
      (footprint "eagle-import:2NOR")
      (libsource (lib "eagle-import") (part "2NOR"))
    )
    (comp (ref "GATE119")
      (value "INVERTER")
      (footprint "eagle-import:INVERTER")
      (libsource (lib "eagle-import") (part "INVERTER"))
    )
    (comp (ref "GATE120")
      (value "3NOR")
      (footprint "eagle-import:3NOR")
      (libsource (lib "eagle-import") (part "3NOR"))
    )
    (comp (ref "GATE121")
      (value "INVERTER")
      (footprint "eagle-import:INVERTER")
      (libsource (lib "eagle-import") (part "INVERTER"))
    )
    (comp (ref "GATE122")
      (value "2NOR")
      (footprint "eagle-import:2NOR")
      (libsource (lib "eagle-import") (part "2NOR"))
    )
    (comp (ref "GATE123")
      (value "INVERTER")
      (footprint "eagle-import:INVERTER")
      (libsource (lib "eagle-import") (part "INVERTER"))
    )
    (comp (ref "GATE124")
      (value "2NOR")
      (footprint "eagle-import:2NOR")
      (libsource (lib "eagle-import") (part "2NOR"))
    )
    (comp (ref "GATE125")
      (value "3NOR")
      (footprint "eagle-import:3NOR")
      (libsource (lib "eagle-import") (part "3NOR"))
    )
    (comp (ref "GATE126")
      (value "2NOR")
      (footprint "eagle-import:2NOR")
      (libsource (lib "eagle-import") (part "2NOR"))
    )
    (comp (ref "GATE127")
      (value "3NOR")
      (footprint "eagle-import:3NOR")
      (libsource (lib "eagle-import") (part "3NOR"))
    )
    (comp (ref "GATE128")
      (value "2NOR")
      (footprint "eagle-import:2NOR")
      (libsource (lib "eagle-import") (part "2NOR"))
    )
    (comp (ref "GATE129")
      (value "2NOR")
      (footprint "eagle-import:2NOR")
      (libsource (lib "eagle-import") (part "2NOR"))
    )
    (comp (ref "GATE130")
      (value "2NOR")
      (footprint "eagle-import:2NOR")
      (libsource (lib "eagle-import") (part "2NOR"))
    )
    (comp (ref "GATE131")
      (value "3NOR")
      (footprint "eagle-import:3NOR")
      (libsource (lib "eagle-import") (part "3NOR"))
    )
    (comp (ref "GATE132")
      (value "3NOR")
      (footprint "eagle-import:3NOR")
      (libsource (lib "eagle-import") (part "3NOR"))
    )
    (comp (ref "GATE133")
      (value "2NOR")
      (footprint "eagle-import:2NOR")
      (libsource (lib "eagle-import") (part "2NOR"))
    )
    (comp (ref "GATE134")
      (value "3NOR")
      (footprint "eagle-import:3NOR")
      (libsource (lib "eagle-import") (part "3NOR"))
    )
    (comp (ref "GATE135")
      (value "3NOR")
      (footprint "eagle-import:3NOR")
      (libsource (lib "eagle-import") (part "3NOR"))
    )
    (comp (ref "GATE136")
      (value "3NOR")
      (footprint "eagle-import:3NOR")
      (libsource (lib "eagle-import") (part "3NOR"))
    )
    (comp (ref "GATE137")
      (value "3NOR")
      (footprint "eagle-import:3NOR")
      (libsource (lib "eagle-import") (part "3NOR"))
    )
    (comp (ref "GATE138")
      (value "3NOR")
      (footprint "eagle-import:3NOR")
      (libsource (lib "eagle-import") (part "3NOR"))
    )
    (comp (ref "GATE139")
      (value "2NOR")
      (footprint "eagle-import:2NOR")
      (libsource (lib "eagle-import") (part "2NOR"))
    )
    (comp (ref "GATE140")
      (value "INVERTER")
      (footprint "eagle-import:INVERTER")
      (libsource (lib "eagle-import") (part "INVERTER"))
    )
    (comp (ref "GATE141")
      (value "4NOR")
      (footprint "eagle-import:4NOR")
      (libsource (lib "eagle-import") (part "4NOR"))
    )
    (comp (ref "GATE142")
      (value "INVERTER")
      (footprint "eagle-import:INVERTER")
      (libsource (lib "eagle-import") (part "INVERTER"))
    )
    (comp (ref "GATE143")
      (value "3NOR")
      (footprint "eagle-import:3NOR")
      (libsource (lib "eagle-import") (part "3NOR"))
    )
    (comp (ref "GATE144")
      (value "INVERTER")
      (footprint "eagle-import:INVERTER")
      (libsource (lib "eagle-import") (part "INVERTER"))
    )
    (comp (ref "GATE145")
      (value "3NOR")
      (footprint "eagle-import:3NOR")
      (libsource (lib "eagle-import") (part "3NOR"))
    )
    (comp (ref "GATE146")
      (value "INVERTER")
      (footprint "eagle-import:INVERTER")
      (libsource (lib "eagle-import") (part "INVERTER"))
    )
    (comp (ref "GATE147")
      (value "2NOR")
      (footprint "eagle-import:2NOR")
      (libsource (lib "eagle-import") (part "2NOR"))
    )
    (comp (ref "GATE148")
      (value "INVERTER")
      (footprint "eagle-import:INVERTER")
      (libsource (lib "eagle-import") (part "INVERTER"))
    )
    (comp (ref "GATE149")
      (value "4NOR")
      (footprint "eagle-import:4NOR")
      (libsource (lib "eagle-import") (part "4NOR"))
    )
    (comp (ref "GATE150")
      (value "INVERTER")
      (footprint "eagle-import:INVERTER")
      (libsource (lib "eagle-import") (part "INVERTER"))
    )
    (comp (ref "GATE151")
      (value "4NOR")
      (footprint "eagle-import:4NOR")
      (libsource (lib "eagle-import") (part "4NOR"))
    )
    (comp (ref "GATE152")
      (value "INVERTER")
      (footprint "eagle-import:INVERTER")
      (libsource (lib "eagle-import") (part "INVERTER"))
    )
    (comp (ref "GATE153")
      (value "3NOR")
      (footprint "eagle-import:3NOR")
      (libsource (lib "eagle-import") (part "3NOR"))
    )
    (comp (ref "GATE154")
      (value "INVERTER")
      (footprint "eagle-import:INVERTER")
      (libsource (lib "eagle-import") (part "INVERTER"))
    )
    (comp (ref "GATE155")
      (value "2NOR")
      (footprint "eagle-import:2NOR")
      (libsource (lib "eagle-import") (part "2NOR"))
    )
    (comp (ref "GATE156")
      (value "INVERTER")
      (footprint "eagle-import:INVERTER")
      (libsource (lib "eagle-import") (part "INVERTER"))
    )
    (comp (ref "GATE157")
      (value "3NOR")
      (footprint "eagle-import:3NOR")
      (libsource (lib "eagle-import") (part "3NOR"))
    )
    (comp (ref "GATE158")
      (value "INVERTER")
      (footprint "eagle-import:INVERTER")
      (libsource (lib "eagle-import") (part "INVERTER"))
    )
    (comp (ref "GATE159")
      (value "4NOR")
      (footprint "eagle-import:4NOR")
      (libsource (lib "eagle-import") (part "4NOR"))
    )
    (comp (ref "GATE160")
      (value "INVERTER")
      (footprint "eagle-import:INVERTER")
      (libsource (lib "eagle-import") (part "INVERTER"))
    )
    (comp (ref "GATE161")
      (value "2NOR")
      (footprint "eagle-import:2NOR")
      (libsource (lib "eagle-import") (part "2NOR"))
    )
    (comp (ref "GATE162")
      (value "INVERTER")
      (footprint "eagle-import:INVERTER")
      (libsource (lib "eagle-import") (part "INVERTER"))
    )
    (comp (ref "GATE163")
      (value "2NOR")
      (footprint "eagle-import:2NOR")
      (libsource (lib "eagle-import") (part "2NOR"))
    )
    (comp (ref "GATE164")
      (value "INVERTER")
      (footprint "eagle-import:INVERTER")
      (libsource (lib "eagle-import") (part "INVERTER"))
    )
    (comp (ref "GATE165")
      (value "4NOR")
      (footprint "eagle-import:4NOR")
      (libsource (lib "eagle-import") (part "4NOR"))
    )
    (comp (ref "GATE166")
      (value "INVERTER")
      (footprint "eagle-import:INVERTER")
      (libsource (lib "eagle-import") (part "INVERTER"))
    )
    (comp (ref "GATE167")
      (value "3NOR")
      (footprint "eagle-import:3NOR")
      (libsource (lib "eagle-import") (part "3NOR"))
    )
    (comp (ref "GATE168")
      (value "INVERTER")
      (footprint "eagle-import:INVERTER")
      (libsource (lib "eagle-import") (part "INVERTER"))
    )
    (comp (ref "GATE169")
      (value "2NOR")
      (footprint "eagle-import:2NOR")
      (libsource (lib "eagle-import") (part "2NOR"))
    )
    (comp (ref "GATE170")
      (value "INVERTER")
      (footprint "eagle-import:INVERTER")
      (libsource (lib "eagle-import") (part "INVERTER"))
    )
    (comp (ref "GATE171")
      (value "2NOR")
      (footprint "eagle-import:2NOR")
      (libsource (lib "eagle-import") (part "2NOR"))
    )
    (comp (ref "GATE172")
      (value "INVERTER")
      (footprint "eagle-import:INVERTER")
      (libsource (lib "eagle-import") (part "INVERTER"))
    )
    (comp (ref "R1")
      (value "0R")
      (footprint "eagle-import:0207_2V")
      (libsource (lib "eagle-import") (part "R-EU_0207/2V"))
    )
    (comp (ref "R2")
      (value "100K")
      (footprint "eagle-import:0207_2V")
      (libsource (lib "eagle-import") (part "R-EU_0207/2V"))
    )
    (comp (ref "R3")
      (value "0R")
      (footprint "eagle-import:0207_2V")
      (libsource (lib "eagle-import") (part "R-EU_0207/2V"))
    )
  )
  (nets
    (net (code "1") (name "DOM_TENS_A") (class "Default")
      (node (ref "B_BUS") (pin "8") (pinfunction "8_8") (pintype "passive"))
      (node (ref "GATE71") (pin "A") (pinfunction "A_A") (pintype "input"))
      (node (ref "GATE75") (pin "A") (pinfunction "A_A") (pintype "input"))
      (node (ref "GATE77") (pin "A") (pinfunction "A_A") (pintype "input"))
      (node (ref "GATE78") (pin "A") (pinfunction "A_A") (pintype "input"))
    )
    (net (code "2") (name "DOM_TENS_B") (class "Default")
      (node (ref "B_BUS") (pin "9") (pinfunction "9_9") (pintype "passive"))
      (node (ref "GATE72") (pin "A") (pinfunction "A_A") (pintype "input"))
      (node (ref "GATE73") (pin "B") (pinfunction "B_B") (pintype "input"))
      (node (ref "GATE78") (pin "B") (pinfunction "B_B") (pintype "input"))
    )
    (net (code "3") (name "DOM_TENS_SEG_AD") (class "Default")
      (node (ref "B_BUS") (pin "39") (pinfunction "39_39") (pintype "passive"))
      (node (ref "GATE74") (pin "Q") (pinfunction "Q_Q") (pintype "output"))
    )
    (net (code "4") (name "DOM_TENS_SEG_B") (class "Default")
      (node (ref "B_BUS") (pin "40") (pinfunction "40_40") (pintype "passive"))
      (node (ref "R2") (pin "2") (pinfunction "2_2") (pintype "passive"))
    )
    (net (code "5") (name "DOM_TENS_SEG_C") (class "Default")
      (node (ref "C_BUS") (pin "1") (pinfunction "1_1") (pintype "passive"))
      (node (ref "GATE76") (pin "Q") (pinfunction "Q_Q") (pintype "output"))
    )
    (net (code "6") (name "DOM_TENS_SEG_E") (class "Default")
      (node (ref "C_BUS") (pin "2") (pinfunction "2_2") (pintype "passive"))
      (node (ref "GATE77") (pin "Q") (pinfunction "Q_Q") (pintype "output"))
    )
    (net (code "7") (name "DOM_TENS_SEG_F") (class "Default")
      (node (ref "C_BUS") (pin "3") (pinfunction "3_3") (pintype "passive"))
      (node (ref "GATE78") (pin "Q") (pinfunction "Q_Q") (pintype "output"))
    )
    (net (code "8") (name "DOM_TENS_SEG_G") (class "Default")
      (node (ref "C_BUS") (pin "4") (pinfunction "4_4") (pintype "passive"))
      (node (ref "GATE79") (pin "Q") (pinfunction "Q_Q") (pintype "output"))
    )
    (net (code "9") (name "DOM_UNIT_A") (class "Default")
      (node (ref "B_BUS") (pin "4") (pinfunction "4_4") (pintype "passive"))
      (node (ref "GATE41") (pin "A") (pinfunction "A_A") (pintype "input"))
      (node (ref "GATE47") (pin "A") (pinfunction "A_A") (pintype "input"))
      (node (ref "GATE50") (pin "A") (pinfunction "A_A") (pintype "input"))
      (node (ref "GATE52") (pin "A") (pinfunction "A_A") (pintype "input"))
      (node (ref "GATE54") (pin "A") (pinfunction "A_A") (pintype "input"))
    )
    (net (code "10") (name "DOM_UNIT_B") (class "Default")
      (node (ref "B_BUS") (pin "5") (pinfunction "5_5") (pintype "passive"))
      (node (ref "GATE42") (pin "A") (pinfunction "A_A") (pintype "input"))
      (node (ref "GATE47") (pin "B") (pinfunction "B_B") (pintype "input"))
      (node (ref "GATE51") (pin "A") (pinfunction "A_A") (pintype "input"))
      (node (ref "GATE52") (pin "B") (pinfunction "B_B") (pintype "input"))
      (node (ref "GATE53") (pin "A") (pinfunction "A_A") (pintype "input"))
      (node (ref "GATE56") (pin "A") (pinfunction "A_A") (pintype "input"))
    )
    (net (code "11") (name "DOM_UNIT_C") (class "Default")
      (node (ref "B_BUS") (pin "6") (pinfunction "6_6") (pintype "passive"))
      (node (ref "GATE43") (pin "A") (pinfunction "A_A") (pintype "input"))
      (node (ref "GATE47") (pin "C") (pinfunction "C_C") (pintype "input"))
      (node (ref "GATE48") (pin "A") (pinfunction "A_A") (pintype "input"))
      (node (ref "GATE51") (pin "B") (pinfunction "B_B") (pintype "input"))
      (node (ref "GATE53") (pin "B") (pinfunction "B_B") (pintype "input"))
    )
    (net (code "12") (name "DOM_UNIT_D") (class "Default")
      (node (ref "B_BUS") (pin "7") (pinfunction "7_7") (pintype "passive"))
      (node (ref "GATE44") (pin "A") (pinfunction "A_A") (pintype "input"))
      (node (ref "GATE45") (pin "A") (pinfunction "A_A") (pintype "input"))
      (node (ref "GATE48") (pin "B") (pinfunction "B_B") (pintype "input"))
      (node (ref "GATE50") (pin "B") (pinfunction "B_B") (pintype "input"))
      (node (ref "GATE55") (pin "A") (pinfunction "A_A") (pintype "input"))
    )
    (net (code "13") (name "DOM_UNIT_SEG_A") (class "Default")
      (node (ref "B_BUS") (pin "32") (pinfunction "32_32") (pintype "passive"))
      (node (ref "GATE58") (pin "Q") (pinfunction "Q_Q") (pintype "output"))
    )
    (net (code "14") (name "DOM_UNIT_SEG_B") (class "Default")
      (node (ref "B_BUS") (pin "33") (pinfunction "33_33") (pintype "passive"))
      (node (ref "GATE60") (pin "Q") (pinfunction "Q_Q") (pintype "output"))
    )
    (net (code "15") (name "DOM_UNIT_SEG_C") (class "Default")
      (node (ref "B_BUS") (pin "34") (pinfunction "34_34") (pintype "passive"))
      (node (ref "GATE62") (pin "Q") (pinfunction "Q_Q") (pintype "output"))
    )
    (net (code "16") (name "DOM_UNIT_SEG_D") (class "Default")
      (node (ref "B_BUS") (pin "35") (pinfunction "35_35") (pintype "passive"))
      (node (ref "GATE64") (pin "Q") (pinfunction "Q_Q") (pintype "output"))
    )
    (net (code "17") (name "DOM_UNIT_SEG_E") (class "Default")
      (node (ref "B_BUS") (pin "36") (pinfunction "36_36") (pintype "passive"))
      (node (ref "GATE66") (pin "Q") (pinfunction "Q_Q") (pintype "output"))
    )
    (net (code "18") (name "DOM_UNIT_SEG_F") (class "Default")
      (node (ref "B_BUS") (pin "37") (pinfunction "37_37") (pintype "passive"))
      (node (ref "GATE68") (pin "Q") (pinfunction "Q_Q") (pintype "output"))
    )
    (net (code "19") (name "DOM_UNIT_SEG_G") (class "Default")
      (node (ref "B_BUS") (pin "38") (pinfunction "38_38") (pintype "passive"))
      (node (ref "GATE70") (pin "Q") (pinfunction "Q_Q") (pintype "output"))
    )
    (net (code "20") (name "DOW_1_SEG_AB") (class "Default")
      (node (ref "B_BUS") (pin "14") (pinfunction "14_14") (pintype "passive"))
      (node (ref "GATE18") (pin "Q") (pinfunction "Q_Q") (pintype "output"))
    )
    (net (code "21") (name "DOW_1_SEG_C") (class "Default")
      (node (ref "B_BUS") (pin "15") (pinfunction "15_15") (pintype "passive"))
      (node (ref "GATE19") (pin "B") (pinfunction "B_B") (pintype "input"))
      (node (ref "GATE23") (pin "A") (pinfunction "A_A") (pintype "input"))
      (node (ref "GATE29") (pin "A") (pinfunction "A_A") (pintype "input"))
      (node (ref "GATE7") (pin "Q") (pinfunction "Q_Q") (pintype "output"))
    )
    (net (code "22") (name "DOW_1_SEG_D") (class "Default")
      (node (ref "B_BUS") (pin "16") (pinfunction "16_16") (pintype "passive"))
      (node (ref "GATE20") (pin "Q") (pinfunction "Q_Q") (pintype "output"))
    )
    (net (code "23") (name "DOW_1_SEG_EF") (class "Default")
      (node (ref "B_BUS") (pin "17") (pinfunction "17_17") (pintype "passive"))
      (node (ref "GATE22") (pin "Q") (pinfunction "Q_Q") (pintype "output"))
    )
    (net (code "24") (name "DOW_1_SEG_GH") (class "Default")
      (node (ref "B_BUS") (pin "18") (pinfunction "18_18") (pintype "passive"))
      (node (ref "GATE24") (pin "Q") (pinfunction "Q_Q") (pintype "output"))
    )
    (net (code "25") (name "DOW_1_SEG_K") (class "Default")
      (node (ref "B_BUS") (pin "19") (pinfunction "19_19") (pintype "passive"))
      (node (ref "GATE26") (pin "Q") (pinfunction "Q_Q") (pintype "output"))
    )
    (net (code "26") (name "DOW_1_SEG_MS") (class "Default")
      (node (ref "B_BUS") (pin "20") (pinfunction "20_20") (pintype "passive"))
      (node (ref "GATE17") (pin "B") (pinfunction "B_B") (pintype "input"))
      (node (ref "GATE31") (pin "B") (pinfunction "B_B") (pintype "input"))
      (node (ref "GATE33") (pin "A") (pinfunction "A_A") (pintype "input"))
      (node (ref "GATE37") (pin "A") (pinfunction "A_A") (pintype "input"))
      (node (ref "GATE5") (pin "Q") (pinfunction "Q_Q") (pintype "output"))
    )
    (net (code "27") (name "DOW_1_SEG_N") (class "Default")
      (node (ref "B_BUS") (pin "21") (pinfunction "21_21") (pintype "passive"))
      (node (ref "GATE10") (pin "Q") (pinfunction "Q_Q") (pintype "output"))
      (node (ref "GATE25") (pin "C") (pinfunction "C_C") (pintype "input"))
    )
    (net (code "28") (name "DOW_1_SEG_P") (class "Default")
      (node (ref "B_BUS") (pin "22") (pinfunction "22_22") (pintype "passive"))
      (node (ref "GATE28") (pin "Q") (pinfunction "Q_Q") (pintype "output"))
    )
    (net (code "29") (name "DOW_1_SEG_RT") (class "Default")
      (node (ref "B_BUS") (pin "23") (pinfunction "23_23") (pintype "passive"))
      (node (ref "GATE11") (pin "Q") (pinfunction "Q_Q") (pintype "output"))
    )
    (net (code "30") (name "DOW_1_SEG_U") (class "Default")
      (node (ref "B_BUS") (pin "24") (pinfunction "24_24") (pintype "passive"))
      (node (ref "GATE23") (pin "B") (pinfunction "B_B") (pintype "input"))
      (node (ref "GATE9") (pin "Q") (pinfunction "Q_Q") (pintype "output"))
      (node (ref "R1") (pin "1") (pinfunction "1_1") (pintype "passive"))
    )
    (net (code "31") (name "DOW_2_SEG_AB") (class "Default")
      (node (ref "B_BUS") (pin "25") (pinfunction "25_25") (pintype "passive"))
      (node (ref "GATE30") (pin "Q") (pinfunction "Q_Q") (pintype "output"))
    )
    (net (code "32") (name "DOW_2_SEG_C") (class "Default")
      (node (ref "B_BUS") (pin "26") (pinfunction "26_26") (pintype "passive"))
      (node (ref "GATE32") (pin "Q") (pinfunction "Q_Q") (pintype "output"))
    )
    (net (code "33") (name "DOW_2_SEG_D") (class "Default")
      (node (ref "B_BUS") (pin "27") (pinfunction "27_27") (pintype "passive"))
      (node (ref "GATE34") (pin "Q") (pinfunction "Q_Q") (pintype "output"))
    )
    (net (code "34") (name "DOW_2_SEG_EF") (class "Default")
      (node (ref "B_BUS") (pin "28") (pinfunction "28_28") (pintype "passive"))
      (node (ref "GATE36") (pin "Q") (pinfunction "Q_Q") (pintype "output"))
    )
    (net (code "35") (name "DOW_2_SEG_GH") (class "Default")
      (node (ref "B_BUS") (pin "29") (pinfunction "29_29") (pintype "passive"))
      (node (ref "GATE38") (pin "Q") (pinfunction "Q_Q") (pintype "output"))
    )
    (net (code "36") (name "DOW_2_SEG_PU") (class "Default")
      (node (ref "B_BUS") (pin "30") (pinfunction "30_30") (pintype "passive"))
      (node (ref "GATE40") (pin "Q") (pinfunction "Q_Q") (pintype "output"))
    )
    (net (code "37") (name "DOW_2_SEG_R") (class "Default")
      (node (ref "B_BUS") (pin "31") (pinfunction "31_31") (pintype "passive"))
      (node (ref "R1") (pin "2") (pinfunction "2_2") (pintype "passive"))
    )
    (net (code "38") (name "DOW_A") (class "Default")
      (node (ref "B_BUS") (pin "1") (pinfunction "1_1") (pintype "passive"))
      (node (ref "GATE1") (pin "A") (pinfunction "A_A") (pintype "input"))
      (node (ref "GATE10") (pin "A") (pinfunction "A_A") (pintype "input"))
      (node (ref "GATE11") (pin "A") (pinfunction "A_A") (pintype "input"))
      (node (ref "GATE13") (pin "A") (pinfunction "A_A") (pintype "input"))
      (node (ref "GATE4") (pin "A") (pinfunction "A_A") (pintype "input"))
      (node (ref "GATE7") (pin "A") (pinfunction "A_A") (pintype "input"))
      (node (ref "GATE8") (pin "A") (pinfunction "A_A") (pintype "input"))
      (node (ref "GATE9") (pin "A") (pinfunction "A_A") (pintype "input"))
    )
    (net (code "39") (name "DOW_B") (class "Default")
      (node (ref "B_BUS") (pin "2") (pinfunction "2_2") (pintype "passive"))
      (node (ref "GATE10") (pin "B") (pinfunction "B_B") (pintype "input"))
      (node (ref "GATE12") (pin "A") (pinfunction "A_A") (pintype "input"))
      (node (ref "GATE14") (pin "A") (pinfunction "A_A") (pintype "input"))
      (node (ref "GATE15") (pin "B") (pinfunction "B_B") (pintype "input"))
      (node (ref "GATE2") (pin "A") (pinfunction "A_A") (pintype "input"))
      (node (ref "GATE6") (pin "B") (pinfunction "B_B") (pintype "input"))
      (node (ref "GATE9") (pin "B") (pinfunction "B_B") (pintype "input"))
    )
    (net (code "40") (name "DOW_C") (class "Default")
      (node (ref "B_BUS") (pin "3") (pinfunction "3_3") (pintype "passive"))
      (node (ref "GATE10") (pin "C") (pinfunction "C_C") (pintype "input"))
      (node (ref "GATE11") (pin "C") (pinfunction "C_C") (pintype "input"))
      (node (ref "GATE14") (pin "B") (pinfunction "B_B") (pintype "input"))
      (node (ref "GATE16") (pin "B") (pinfunction "B_B") (pintype "input"))
      (node (ref "GATE3") (pin "A") (pinfunction "A_A") (pintype "input"))
      (node (ref "GATE5") (pin "B") (pinfunction "B_B") (pintype "input"))
      (node (ref "GATE7") (pin "B") (pinfunction "B_B") (pintype "input"))
    )
    (net (code "41") (name "HRS_TENS_SEG_AD") (class "Default")
      (node (ref "D_BUS") (pin "34") (pinfunction "34_34") (pintype "passive"))
    )
    (net (code "42") (name "HRS_TENS_SEG_B") (class "Default")
      (node (ref "D_BUS") (pin "35") (pinfunction "35_35") (pintype "passive"))
    )
    (net (code "43") (name "HRS_TENS_SEG_C") (class "Default")
      (node (ref "D_BUS") (pin "36") (pinfunction "36_36") (pintype "passive"))
    )
    (net (code "44") (name "HRS_TENS_SEG_E") (class "Default")
      (node (ref "D_BUS") (pin "37") (pinfunction "37_37") (pintype "passive"))
    )
    (net (code "45") (name "HRS_TENS_SEG_F") (class "Default")
      (node (ref "D_BUS") (pin "38") (pinfunction "38_38") (pintype "passive"))
    )
    (net (code "46") (name "HRS_TENS_SEG_G") (class "Default")
      (node (ref "D_BUS") (pin "39") (pinfunction "39_39") (pintype "passive"))
    )
    (net (code "47") (name "HRS_UNIT_SEG_A") (class "Default")
      (node (ref "D_BUS") (pin "27") (pinfunction "27_27") (pintype "passive"))
    )
    (net (code "48") (name "HRS_UNIT_SEG_B") (class "Default")
      (node (ref "D_BUS") (pin "28") (pinfunction "28_28") (pintype "passive"))
    )
    (net (code "49") (name "HRS_UNIT_SEG_C") (class "Default")
      (node (ref "D_BUS") (pin "29") (pinfunction "29_29") (pintype "passive"))
    )
    (net (code "50") (name "HRS_UNIT_SEG_D") (class "Default")
      (node (ref "D_BUS") (pin "30") (pinfunction "30_30") (pintype "passive"))
    )
    (net (code "51") (name "HRS_UNIT_SEG_E") (class "Default")
      (node (ref "D_BUS") (pin "31") (pinfunction "31_31") (pintype "passive"))
    )
    (net (code "52") (name "HRS_UNIT_SEG_F") (class "Default")
      (node (ref "D_BUS") (pin "32") (pinfunction "32_32") (pintype "passive"))
    )
    (net (code "53") (name "HRS_UNIT_SEG_G") (class "Default")
      (node (ref "D_BUS") (pin "33") (pinfunction "33_33") (pintype "passive"))
    )
    (net (code "54") (name "MIN_TENS_SEG_AD") (class "Default")
      (node (ref "D_BUS") (pin "21") (pinfunction "21_21") (pintype "passive"))
    )
    (net (code "55") (name "MIN_TENS_SEG_B") (class "Default")
      (node (ref "D_BUS") (pin "22") (pinfunction "22_22") (pintype "passive"))
    )
    (net (code "56") (name "MIN_TENS_SEG_C") (class "Default")
      (node (ref "D_BUS") (pin "23") (pinfunction "23_23") (pintype "passive"))
    )
    (net (code "57") (name "MIN_TENS_SEG_E") (class "Default")
      (node (ref "D_BUS") (pin "24") (pinfunction "24_24") (pintype "passive"))
    )
    (net (code "58") (name "MIN_TENS_SEG_F") (class "Default")
      (node (ref "D_BUS") (pin "25") (pinfunction "25_25") (pintype "passive"))
    )
    (net (code "59") (name "MIN_TENS_SEG_G") (class "Default")
      (node (ref "D_BUS") (pin "26") (pinfunction "26_26") (pintype "passive"))
    )
    (net (code "60") (name "MIN_UNIT_SEG_A") (class "Default")
      (node (ref "D_BUS") (pin "14") (pinfunction "14_14") (pintype "passive"))
    )
    (net (code "61") (name "MIN_UNIT_SEG_B") (class "Default")
      (node (ref "D_BUS") (pin "15") (pinfunction "15_15") (pintype "passive"))
    )
    (net (code "62") (name "MIN_UNIT_SEG_C") (class "Default")
      (node (ref "D_BUS") (pin "16") (pinfunction "16_16") (pintype "passive"))
    )
    (net (code "63") (name "MIN_UNIT_SEG_D") (class "Default")
      (node (ref "D_BUS") (pin "17") (pinfunction "17_17") (pintype "passive"))
    )
    (net (code "64") (name "MIN_UNIT_SEG_E") (class "Default")
      (node (ref "D_BUS") (pin "18") (pinfunction "18_18") (pintype "passive"))
    )
    (net (code "65") (name "MIN_UNIT_SEG_F") (class "Default")
      (node (ref "D_BUS") (pin "19") (pinfunction "19_19") (pintype "passive"))
    )
    (net (code "66") (name "MIN_UNIT_SEG_G") (class "Default")
      (node (ref "D_BUS") (pin "20") (pinfunction "20_20") (pintype "passive"))
    )
    (net (code "67") (name "MON_1_SEG_AB") (class "Default")
      (node (ref "C_BUS") (pin "5") (pinfunction "5_5") (pintype "passive"))
      (node (ref "GATE105") (pin "Q") (pinfunction "Q_Q") (pintype "output"))
    )
    (net (code "68") (name "MON_1_SEG_C") (class "Default")
      (node (ref "C_BUS") (pin "6") (pinfunction "6_6") (pintype "passive"))
      (node (ref "GATE107") (pin "Q") (pinfunction "Q_Q") (pintype "output"))
    )
    (net (code "69") (name "MON_1_SEG_D") (class "Default")
      (node (ref "C_BUS") (pin "7") (pinfunction "7_7") (pintype "passive"))
      (node (ref "GATE109") (pin "Q") (pinfunction "Q_Q") (pintype "output"))
    )
    (net (code "70") (name "MON_1_SEG_EF") (class "Default")
      (node (ref "C_BUS") (pin "8") (pinfunction "8_8") (pintype "passive"))
      (node (ref "GATE111") (pin "Q") (pinfunction "Q_Q") (pintype "output"))
    )
    (net (code "71") (name "MON_1_SEG_G") (class "Default")
      (node (ref "C_BUS") (pin "9") (pinfunction "9_9") (pintype "passive"))
      (node (ref "GATE113") (pin "Q") (pinfunction "Q_Q") (pintype "output"))
    )
    (net (code "72") (name "MON_1_SEG_H") (class "Default")
      (node (ref "C_BUS") (pin "10") (pinfunction "10_10") (pintype "passive"))
      (node (ref "GATE115") (pin "Q") (pinfunction "Q_Q") (pintype "output"))
    )
    (net (code "73") (name "MON_1_SEG_K") (class "Default")
      (node (ref "C_BUS") (pin "11") (pinfunction "11_11") (pintype "passive"))
      (node (ref "GATE117") (pin "Q") (pinfunction "Q_Q") (pintype "output"))
    )
    (net (code "74") (name "MON_1_SEG_MS") (class "Default")
      (node (ref "C_BUS") (pin "12") (pinfunction "12_12") (pintype "passive"))
      (node (ref "GATE131") (pin "Q") (pinfunction "Q_Q") (pintype "output"))
      (node (ref "GATE157") (pin "B") (pinfunction "B_B") (pintype "input"))
    )
    (net (code "75") (name "MON_1_SEG_N") (class "Default")
      (node (ref "C_BUS") (pin "13") (pinfunction "13_13") (pintype "passive"))
      (node (ref "GATE119") (pin "Q") (pinfunction "Q_Q") (pintype "output"))
    )
    (net (code "76") (name "MON_1_SEG_P") (class "Default")
      (node (ref "C_BUS") (pin "14") (pinfunction "14_14") (pintype "passive"))
      (node (ref "GATE121") (pin "Q") (pinfunction "Q_Q") (pintype "output"))
    )
    (net (code "77") (name "MON_1_SEG_R") (class "Default")
      (node (ref "C_BUS") (pin "15") (pinfunction "15_15") (pintype "passive"))
      (node (ref "GATE137") (pin "Q") (pinfunction "Q_Q") (pintype "output"))
      (node (ref "GATE163") (pin "A") (pinfunction "A_A") (pintype "input"))
      (node (ref "R3") (pin "1") (pinfunction "1_1") (pintype "passive"))
    )
    (net (code "78") (name "MON_1_SEG_U") (class "Default")
      (node (ref "C_BUS") (pin "16") (pinfunction "16_16") (pintype "passive"))
      (node (ref "GATE123") (pin "Q") (pinfunction "Q_Q") (pintype "output"))
    )
    (net (code "79") (name "MON_2_SEG_AB") (class "Default")
      (node (ref "C_BUS") (pin "17") (pinfunction "17_17") (pintype "passive"))
      (node (ref "GATE140") (pin "Q") (pinfunction "Q_Q") (pintype "output"))
    )
    (net (code "80") (name "MON_2_SEG_C") (class "Default")
      (node (ref "C_BUS") (pin "18") (pinfunction "18_18") (pintype "passive"))
      (node (ref "GATE142") (pin "Q") (pinfunction "Q_Q") (pintype "output"))
    )
    (net (code "81") (name "MON_2_SEG_D") (class "Default")
      (node (ref "C_BUS") (pin "19") (pinfunction "19_19") (pintype "passive"))
      (node (ref "GATE144") (pin "Q") (pinfunction "Q_Q") (pintype "output"))
    )
    (net (code "82") (name "MON_2_SEG_EF") (class "Default")
      (node (ref "C_BUS") (pin "20") (pinfunction "20_20") (pintype "passive"))
      (node (ref "GATE146") (pin "Q") (pinfunction "Q_Q") (pintype "output"))
    )
    (net (code "83") (name "MON_2_SEG_GH") (class "Default")
      (node (ref "C_BUS") (pin "21") (pinfunction "21_21") (pintype "passive"))
      (node (ref "GATE148") (pin "Q") (pinfunction "Q_Q") (pintype "output"))
    )
    (net (code "84") (name "MON_2_SEG_PU") (class "Default")
      (node (ref "C_BUS") (pin "22") (pinfunction "22_22") (pintype "passive"))
      (node (ref "GATE150") (pin "Q") (pinfunction "Q_Q") (pintype "output"))
    )
    (net (code "85") (name "MON_3_SEG_AB") (class "Default")
      (node (ref "C_BUS") (pin "23") (pinfunction "23_23") (pintype "passive"))
      (node (ref "GATE152") (pin "Q") (pinfunction "Q_Q") (pintype "output"))
    )
    (net (code "86") (name "MON_3_SEG_C") (class "Default")
      (node (ref "C_BUS") (pin "24") (pinfunction "24_24") (pintype "passive"))
      (node (ref "GATE154") (pin "Q") (pinfunction "Q_Q") (pintype "output"))
    )
    (net (code "87") (name "MON_3_SEG_D") (class "Default")
      (node (ref "C_BUS") (pin "25") (pinfunction "25_25") (pintype "passive"))
      (node (ref "GATE156") (pin "Q") (pinfunction "Q_Q") (pintype "output"))
    )
    (net (code "88") (name "MON_3_SEG_EF") (class "Default")
      (node (ref "C_BUS") (pin "26") (pinfunction "26_26") (pintype "passive"))
      (node (ref "GATE158") (pin "Q") (pinfunction "Q_Q") (pintype "output"))
    )
    (net (code "89") (name "MON_3_SEG_GH") (class "Default")
      (node (ref "C_BUS") (pin "27") (pinfunction "27_27") (pintype "passive"))
      (node (ref "GATE160") (pin "Q") (pinfunction "Q_Q") (pintype "output"))
    )
    (net (code "90") (name "MON_3_SEG_K") (class "Default")
      (node (ref "C_BUS") (pin "28") (pinfunction "28_28") (pintype "passive"))
      (node (ref "GATE162") (pin "Q") (pinfunction "Q_Q") (pintype "output"))
    )
    (net (code "91") (name "MON_3_SEG_M") (class "Default")
      (node (ref "C_BUS") (pin "29") (pinfunction "29_29") (pintype "passive"))
      (node (ref "GATE103") (pin "Q") (pinfunction "Q_Q") (pintype "output"))
      (node (ref "GATE112") (pin "B") (pinfunction "B_B") (pintype "input"))
      (node (ref "GATE114") (pin "B") (pinfunction "B_B") (pintype "input"))
      (node (ref "GATE169") (pin "B") (pinfunction "B_B") (pintype "input"))
    )
    (net (code "92") (name "MON_3_SEG_N") (class "Default")
      (node (ref "C_BUS") (pin "30") (pinfunction "30_30") (pintype "passive"))
      (node (ref "GATE164") (pin "Q") (pinfunction "Q_Q") (pintype "output"))
    )
    (net (code "93") (name "MON_3_SEG_P") (class "Default")
      (node (ref "C_BUS") (pin "31") (pinfunction "31_31") (pintype "passive"))
      (node (ref "GATE166") (pin "Q") (pinfunction "Q_Q") (pintype "output"))
    )
    (net (code "94") (name "MON_3_SEG_R") (class "Default")
      (node (ref "C_BUS") (pin "32") (pinfunction "32_32") (pintype "passive"))
      (node (ref "GATE168") (pin "Q") (pinfunction "Q_Q") (pintype "output"))
    )
    (net (code "95") (name "MON_3_SEG_S") (class "Default")
      (node (ref "C_BUS") (pin "33") (pinfunction "33_33") (pintype "passive"))
      (node (ref "GATE170") (pin "Q") (pinfunction "Q_Q") (pintype "output"))
    )
    (net (code "96") (name "MON_3_SEG_T") (class "Default")
      (node (ref "C_BUS") (pin "34") (pinfunction "34_34") (pintype "passive"))
      (node (ref "R3") (pin "2") (pinfunction "2_2") (pintype "passive"))
    )
    (net (code "97") (name "MON_3_SEG_U") (class "Default")
      (node (ref "C_BUS") (pin "35") (pinfunction "35_35") (pintype "passive"))
      (node (ref "GATE172") (pin "Q") (pinfunction "Q_Q") (pintype "output"))
    )
    (net (code "98") (name "MON_A") (class "Default")
      (node (ref "B_BUS") (pin "10") (pinfunction "10_10") (pintype "passive"))
      (node (ref "GATE134") (pin "A") (pinfunction "A_A") (pintype "input"))
      (node (ref "GATE136") (pin "A") (pinfunction "A_A") (pintype "input"))
      (node (ref "GATE80") (pin "A") (pinfunction "A_A") (pintype "input"))
      (node (ref "GATE92") (pin "A") (pinfunction "A_A") (pintype "input"))
      (node (ref "GATE98") (pin "A") (pinfunction "A_A") (pintype "input"))
    )
    (net (code "99") (name "MON_B") (class "Default")
      (node (ref "B_BUS") (pin "11") (pinfunction "11_11") (pintype "passive"))
      (node (ref "GATE101") (pin "A") (pinfunction "A_A") (pintype "input"))
      (node (ref "GATE103") (pin "A") (pinfunction "A_A") (pintype "input"))
      (node (ref "GATE125") (pin "A") (pinfunction "A_A") (pintype "input"))
      (node (ref "GATE129") (pin "A") (pinfunction "A_A") (pintype "input"))
      (node (ref "GATE132") (pin "A") (pinfunction "A_A") (pintype "input"))
      (node (ref "GATE133") (pin "A") (pinfunction "A_A") (pintype "input"))
      (node (ref "GATE135") (pin "A") (pinfunction "A_A") (pintype "input"))
      (node (ref "GATE136") (pin "B") (pinfunction "B_B") (pintype "input"))
      (node (ref "GATE138") (pin "A") (pinfunction "A_A") (pintype "input"))
      (node (ref "GATE81") (pin "A") (pinfunction "A_A") (pintype "input"))
      (node (ref "GATE97") (pin "A") (pinfunction "A_A") (pintype "input"))
      (node (ref "GATE98") (pin "B") (pinfunction "B_B") (pintype "input"))
    )
    (net (code "100") (name "MON_C") (class "Default")
      (node (ref "B_BUS") (pin "12") (pinfunction "12_12") (pintype "passive"))
      (node (ref "GATE103") (pin "B") (pinfunction "B_B") (pintype "input"))
      (node (ref "GATE127") (pin "A") (pinfunction "A_A") (pintype "input"))
      (node (ref "GATE82") (pin "A") (pinfunction "A_A") (pintype "input"))
      (node (ref "GATE84") (pin "A") (pinfunction "A_A") (pintype "input"))
      (node (ref "GATE87") (pin "A") (pinfunction "A_A") (pintype "input"))
      (node (ref "GATE88") (pin "A") (pinfunction "A_A") (pintype "input"))
      (node (ref "GATE90") (pin "A") (pinfunction "A_A") (pintype "input"))
      (node (ref "GATE92") (pin "B") (pinfunction "B_B") (pintype "input"))
    )
    (net (code "101") (name "MON_D") (class "Default")
      (node (ref "B_BUS") (pin "13") (pinfunction "13_13") (pintype "passive"))
      (node (ref "GATE125") (pin "B") (pinfunction "B_B") (pintype "input"))
      (node (ref "GATE126") (pin "A") (pinfunction "A_A") (pintype "input"))
      (node (ref "GATE83") (pin "A") (pinfunction "A_A") (pintype "input"))
      (node (ref "GATE85") (pin "A") (pinfunction "A_A") (pintype "input"))
      (node (ref "GATE90") (pin "B") (pinfunction "B_B") (pintype "input"))
      (node (ref "GATE95") (pin "A") (pinfunction "A_A") (pintype "input"))
      (node (ref "GATE96") (pin "A") (pinfunction "A_A") (pintype "input"))
      (node (ref "GATE98") (pin "C") (pinfunction "C_C") (pintype "input"))
    )
    (net (code "102") (name "Net-(GATE1-PadQ)") (class "Default")
      (node (ref "GATE1") (pin "Q") (pinfunction "Q_Q") (pintype "output"))
      (node (ref "GATE15") (pin "A") (pinfunction "A_A") (pintype "input"))
      (node (ref "GATE37") (pin "C") (pinfunction "C_C") (pintype "input"))
      (node (ref "GATE5") (pin "A") (pinfunction "A_A") (pintype "input"))
      (node (ref "GATE6") (pin "A") (pinfunction "A_A") (pintype "input"))
    )
    (net (code "103") (name "Net-(GATE11-PadB)") (class "Default")
      (node (ref "GATE11") (pin "B") (pinfunction "B_B") (pintype "input"))
      (node (ref "GATE13") (pin "B") (pinfunction "B_B") (pintype "input"))
      (node (ref "GATE16") (pin "A") (pinfunction "A_A") (pintype "input"))
      (node (ref "GATE2") (pin "Q") (pinfunction "Q_Q") (pintype "output"))
      (node (ref "GATE31") (pin "C") (pinfunction "C_C") (pintype "input"))
      (node (ref "GATE8") (pin "B") (pinfunction "B_B") (pintype "input"))
    )
    (net (code "104") (name "Net-(GATE12-PadB)") (class "Default")
      (node (ref "GATE12") (pin "B") (pinfunction "B_B") (pintype "input"))
      (node (ref "GATE3") (pin "Q") (pinfunction "Q_Q") (pintype "output"))
      (node (ref "GATE4") (pin "B") (pinfunction "B_B") (pintype "input"))
      (node (ref "GATE6") (pin "C") (pinfunction "C_C") (pintype "input"))
      (node (ref "GATE8") (pin "C") (pinfunction "C_C") (pintype "input"))
      (node (ref "GATE9") (pin "C") (pinfunction "C_C") (pintype "input"))
    )
    (net (code "105") (name "Net-(GATE12-PadQ)") (class "Default")
      (node (ref "GATE12") (pin "Q") (pinfunction "Q_Q") (pintype "output"))
      (node (ref "GATE27") (pin "B") (pinfunction "B_B") (pintype "input"))
      (node (ref "GATE29") (pin "B") (pinfunction "B_B") (pintype "input"))
      (node (ref "GATE39") (pin "A") (pinfunction "A_A") (pintype "input"))
    )
    (net (code "106") (name "Net-(GATE13-PadQ)") (class "Default")
      (node (ref "GATE13") (pin "Q") (pinfunction "Q_Q") (pintype "output"))
      (node (ref "GATE19") (pin "C") (pinfunction "C_C") (pintype "input"))
      (node (ref "GATE35") (pin "A") (pinfunction "A_A") (pintype "input"))
    )
    (net (code "107") (name "Net-(GATE14-PadQ)") (class "Default")
      (node (ref "GATE14") (pin "Q") (pinfunction "Q_Q") (pintype "output"))
      (node (ref "GATE33") (pin "C") (pinfunction "C_C") (pintype "input"))
      (node (ref "GATE35") (pin "B") (pinfunction "B_B") (pintype "input"))
    )
    (net (code "108") (name "Net-(GATE15-PadQ)") (class "Default")
      (node (ref "GATE15") (pin "Q") (pinfunction "Q_Q") (pintype "output"))
      (node (ref "GATE17") (pin "C") (pinfunction "C_C") (pintype "input"))
      (node (ref "GATE33") (pin "D") (pinfunction "D_D") (pintype "input"))
      (node (ref "GATE37") (pin "B") (pinfunction "B_B") (pintype "input"))
    )
    (net (code "109") (name "Net-(GATE16-PadQ)") (class "Default")
      (node (ref "GATE16") (pin "Q") (pinfunction "Q_Q") (pintype "output"))
      (node (ref "GATE39") (pin "B") (pinfunction "B_B") (pintype "input"))
    )
    (net (code "110") (name "Net-(GATE17-PadA)") (class "Default")
      (node (ref "GATE17") (pin "A") (pinfunction "A_A") (pintype "input"))
      (node (ref "GATE27") (pin "A") (pinfunction "A_A") (pintype "input"))
      (node (ref "GATE31") (pin "A") (pinfunction "A_A") (pintype "input"))
      (node (ref "GATE4") (pin "Q") (pinfunction "Q_Q") (pintype "output"))
    )
    (net (code "111") (name "Net-(GATE17-PadQ)") (class "Default")
      (node (ref "GATE17") (pin "Q") (pinfunction "Q_Q") (pintype "output"))
      (node (ref "GATE18") (pin "A") (pinfunction "A_A") (pintype "input"))
    )
    (net (code "112") (name "Net-(GATE19-PadA)") (class "Default")
      (node (ref "GATE19") (pin "A") (pinfunction "A_A") (pintype "input"))
      (node (ref "GATE21") (pin "A") (pinfunction "A_A") (pintype "input"))
      (node (ref "GATE25") (pin "A") (pinfunction "A_A") (pintype "input"))
      (node (ref "GATE6") (pin "Q") (pinfunction "Q_Q") (pintype "output"))
    )
    (net (code "113") (name "Net-(GATE19-PadQ)") (class "Default")
      (node (ref "GATE19") (pin "Q") (pinfunction "Q_Q") (pintype "output"))
      (node (ref "GATE20") (pin "A") (pinfunction "A_A") (pintype "input"))
    )
    (net (code "114") (name "Net-(GATE21-PadB)") (class "Default")
      (node (ref "GATE21") (pin "B") (pinfunction "B_B") (pintype "input"))
      (node (ref "GATE25") (pin "B") (pinfunction "B_B") (pintype "input"))
      (node (ref "GATE33") (pin "B") (pinfunction "B_B") (pintype "input"))
      (node (ref "GATE8") (pin "Q") (pinfunction "Q_Q") (pintype "output"))
    )
    (net (code "115") (name "Net-(GATE21-PadQ)") (class "Default")
      (node (ref "GATE21") (pin "Q") (pinfunction "Q_Q") (pintype "output"))
      (node (ref "GATE22") (pin "A") (pinfunction "A_A") (pintype "input"))
    )
    (net (code "116") (name "Net-(GATE23-PadQ)") (class "Default")
      (node (ref "GATE23") (pin "Q") (pinfunction "Q_Q") (pintype "output"))
      (node (ref "GATE24") (pin "A") (pinfunction "A_A") (pintype "input"))
    )
    (net (code "117") (name "Net-(GATE25-PadQ)") (class "Default")
      (node (ref "GATE25") (pin "Q") (pinfunction "Q_Q") (pintype "output"))
      (node (ref "GATE26") (pin "A") (pinfunction "A_A") (pintype "input"))
    )
    (net (code "118") (name "Net-(GATE27-PadQ)") (class "Default")
      (node (ref "GATE27") (pin "Q") (pinfunction "Q_Q") (pintype "output"))
      (node (ref "GATE28") (pin "A") (pinfunction "A_A") (pintype "input"))
    )
    (net (code "119") (name "Net-(GATE29-PadQ)") (class "Default")
      (node (ref "GATE29") (pin "Q") (pinfunction "Q_Q") (pintype "output"))
      (node (ref "GATE30") (pin "A") (pinfunction "A_A") (pintype "input"))
    )
    (net (code "120") (name "Net-(GATE31-PadQ)") (class "Default")
      (node (ref "GATE31") (pin "Q") (pinfunction "Q_Q") (pintype "output"))
      (node (ref "GATE32") (pin "A") (pinfunction "A_A") (pintype "input"))
    )
    (net (code "121") (name "Net-(GATE33-PadQ)") (class "Default")
      (node (ref "GATE33") (pin "Q") (pinfunction "Q_Q") (pintype "output"))
      (node (ref "GATE34") (pin "A") (pinfunction "A_A") (pintype "input"))
    )
    (net (code "122") (name "Net-(GATE35-PadQ)") (class "Default")
      (node (ref "GATE35") (pin "Q") (pinfunction "Q_Q") (pintype "output"))
      (node (ref "GATE36") (pin "A") (pinfunction "A_A") (pintype "input"))
    )
    (net (code "123") (name "Net-(GATE37-PadQ)") (class "Default")
      (node (ref "GATE37") (pin "Q") (pinfunction "Q_Q") (pintype "output"))
      (node (ref "GATE38") (pin "A") (pinfunction "A_A") (pintype "input"))
    )
    (net (code "124") (name "Net-(GATE39-PadQ)") (class "Default")
      (node (ref "GATE39") (pin "Q") (pinfunction "Q_Q") (pintype "output"))
      (node (ref "GATE40") (pin "A") (pinfunction "A_A") (pintype "input"))
    )
    (net (code "125") (name "Net-(GATE41-PadQ)") (class "Default")
      (node (ref "GATE41") (pin "Q") (pinfunction "Q_Q") (pintype "output"))
      (node (ref "GATE49") (pin "A") (pinfunction "A_A") (pintype "input"))
      (node (ref "GATE53") (pin "C") (pinfunction "C_C") (pintype "input"))
      (node (ref "GATE55") (pin "B") (pinfunction "B_B") (pintype "input"))
      (node (ref "GATE56") (pin "B") (pinfunction "B_B") (pintype "input"))
    )
    (net (code "126") (name "Net-(GATE42-PadQ)") (class "Default")
      (node (ref "GATE42") (pin "Q") (pinfunction "Q_Q") (pintype "output"))
      (node (ref "GATE48") (pin "C") (pinfunction "C_C") (pintype "input"))
      (node (ref "GATE50") (pin "C") (pinfunction "C_C") (pintype "input"))
      (node (ref "GATE55") (pin "C") (pinfunction "C_C") (pintype "input"))
    )
    (net (code "127") (name "Net-(GATE43-PadQ)") (class "Default")
      (node (ref "GATE43") (pin "Q") (pinfunction "Q_Q") (pintype "output"))
      (node (ref "GATE45") (pin "B") (pinfunction "B_B") (pintype "input"))
    )
    (net (code "128") (name "Net-(GATE44-PadQ)") (class "Default")
      (node (ref "GATE44") (pin "Q") (pinfunction "Q_Q") (pintype "output"))
      (node (ref "GATE51") (pin "C") (pinfunction "C_C") (pintype "input"))
    )
    (net (code "129") (name "Net-(GATE45-PadQ)") (class "Default")
      (node (ref "GATE45") (pin "Q") (pinfunction "Q_Q") (pintype "output"))
      (node (ref "GATE46") (pin "A") (pinfunction "A_A") (pintype "input"))
    )
    (net (code "130") (name "Net-(GATE46-PadQ)") (class "Default")
      (node (ref "GATE46") (pin "Q") (pinfunction "Q_Q") (pintype "output"))
      (node (ref "GATE49") (pin "B") (pinfunction "B_B") (pintype "input"))
      (node (ref "GATE52") (pin "C") (pinfunction "C_C") (pintype "input"))
      (node (ref "GATE54") (pin "B") (pinfunction "B_B") (pintype "input"))
      (node (ref "GATE56") (pin "C") (pinfunction "C_C") (pintype "input"))
    )
    (net (code "131") (name "Net-(GATE47-PadQ)") (class "Default")
      (node (ref "GATE47") (pin "Q") (pinfunction "Q_Q") (pintype "output"))
      (node (ref "GATE57") (pin "A") (pinfunction "A_A") (pintype "input"))
      (node (ref "GATE59") (pin "A") (pinfunction "A_A") (pintype "input"))
      (node (ref "GATE61") (pin "A") (pinfunction "A_A") (pintype "input"))
      (node (ref "GATE63") (pin "A") (pinfunction "A_A") (pintype "input"))
      (node (ref "GATE65") (pin "A") (pinfunction "A_A") (pintype "input"))
      (node (ref "GATE67") (pin "A") (pinfunction "A_A") (pintype "input"))
    )
    (net (code "132") (name "Net-(GATE48-PadQ)") (class "Default")
      (node (ref "GATE48") (pin "Q") (pinfunction "Q_Q") (pintype "output"))
      (node (ref "GATE57") (pin "B") (pinfunction "B_B") (pintype "input"))
      (node (ref "GATE59") (pin "B") (pinfunction "B_B") (pintype "input"))
      (node (ref "GATE63") (pin "B") (pinfunction "B_B") (pintype "input"))
      (node (ref "GATE69") (pin "A") (pinfunction "A_A") (pintype "input"))
    )
    (net (code "133") (name "Net-(GATE49-PadQ)") (class "Default")
      (node (ref "GATE49") (pin "Q") (pinfunction "Q_Q") (pintype "output"))
      (node (ref "GATE57") (pin "C") (pinfunction "C_C") (pintype "input"))
      (node (ref "GATE61") (pin "B") (pinfunction "B_B") (pintype "input"))
    )
    (net (code "134") (name "Net-(GATE50-PadQ)") (class "Default")
      (node (ref "GATE50") (pin "Q") (pinfunction "Q_Q") (pintype "output"))
      (node (ref "GATE57") (pin "D") (pinfunction "D_D") (pintype "input"))
      (node (ref "GATE63") (pin "C") (pinfunction "C_C") (pintype "input"))
      (node (ref "GATE65") (pin "B") (pinfunction "B_B") (pintype "input"))
    )
    (net (code "135") (name "Net-(GATE51-PadQ)") (class "Default")
      (node (ref "GATE51") (pin "Q") (pinfunction "Q_Q") (pintype "output"))
      (node (ref "GATE57") (pin "E") (pinfunction "E_E") (pintype "input"))
      (node (ref "GATE63") (pin "D") (pinfunction "D_D") (pintype "input"))
      (node (ref "GATE67") (pin "B") (pinfunction "B_B") (pintype "input"))
      (node (ref "GATE69") (pin "B") (pinfunction "B_B") (pintype "input"))
    )
    (net (code "136") (name "Net-(GATE52-PadQ)") (class "Default")
      (node (ref "GATE52") (pin "Q") (pinfunction "Q_Q") (pintype "output"))
      (node (ref "GATE59") (pin "C") (pinfunction "C_C") (pintype "input"))
    )
    (net (code "137") (name "Net-(GATE53-PadQ)") (class "Default")
      (node (ref "GATE53") (pin "Q") (pinfunction "Q_Q") (pintype "output"))
      (node (ref "GATE59") (pin "D") (pinfunction "D_D") (pintype "input"))
      (node (ref "GATE61") (pin "C") (pinfunction "C_C") (pintype "input"))
    )
    (net (code "138") (name "Net-(GATE54-PadQ)") (class "Default")
      (node (ref "GATE54") (pin "Q") (pinfunction "Q_Q") (pintype "output"))
      (node (ref "GATE61") (pin "D") (pinfunction "D_D") (pintype "input"))
      (node (ref "GATE67") (pin "C") (pinfunction "C_C") (pintype "input"))
      (node (ref "GATE69") (pin "C") (pinfunction "C_C") (pintype "input"))
    )
    (net (code "139") (name "Net-(GATE55-PadQ)") (class "Default")
      (node (ref "GATE55") (pin "Q") (pinfunction "Q_Q") (pintype "output"))
      (node (ref "GATE59") (pin "E") (pinfunction "E_E") (pintype "input"))
      (node (ref "GATE61") (pin "E") (pinfunction "E_E") (pintype "input"))
    )
    (net (code "140") (name "Net-(GATE56-PadQ)") (class "Default")
      (node (ref "GATE56") (pin "Q") (pinfunction "Q_Q") (pintype "output"))
      (node (ref "GATE63") (pin "E") (pinfunction "E_E") (pintype "input"))
      (node (ref "GATE67") (pin "D") (pinfunction "D_D") (pintype "input"))
      (node (ref "GATE69") (pin "D") (pinfunction "D_D") (pintype "input"))
    )
    (net (code "141") (name "Net-(GATE57-PadQ)") (class "Default")
      (node (ref "GATE57") (pin "Q") (pinfunction "Q_Q") (pintype "output"))
      (node (ref "GATE58") (pin "A") (pinfunction "A_A") (pintype "input"))
    )
    (net (code "142") (name "Net-(GATE59-PadQ)") (class "Default")
      (node (ref "GATE59") (pin "Q") (pinfunction "Q_Q") (pintype "output"))
      (node (ref "GATE60") (pin "A") (pinfunction "A_A") (pintype "input"))
    )
    (net (code "143") (name "Net-(GATE61-PadQ)") (class "Default")
      (node (ref "GATE61") (pin "Q") (pinfunction "Q_Q") (pintype "output"))
      (node (ref "GATE62") (pin "A") (pinfunction "A_A") (pintype "input"))
    )
    (net (code "144") (name "Net-(GATE63-PadQ)") (class "Default")
      (node (ref "GATE63") (pin "Q") (pinfunction "Q_Q") (pintype "output"))
      (node (ref "GATE64") (pin "A") (pinfunction "A_A") (pintype "input"))
    )
    (net (code "145") (name "Net-(GATE65-PadQ)") (class "Default")
      (node (ref "GATE65") (pin "Q") (pinfunction "Q_Q") (pintype "output"))
      (node (ref "GATE66") (pin "A") (pinfunction "A_A") (pintype "input"))
    )
    (net (code "146") (name "Net-(GATE67-PadQ)") (class "Default")
      (node (ref "GATE67") (pin "Q") (pinfunction "Q_Q") (pintype "output"))
      (node (ref "GATE68") (pin "A") (pinfunction "A_A") (pintype "input"))
    )
    (net (code "147") (name "Net-(GATE69-PadQ)") (class "Default")
      (node (ref "GATE69") (pin "Q") (pinfunction "Q_Q") (pintype "output"))
      (node (ref "GATE70") (pin "A") (pinfunction "A_A") (pintype "input"))
    )
    (net (code "148") (name "Net-(GATE71-PadQ)") (class "Default")
      (node (ref "GATE71") (pin "Q") (pinfunction "Q_Q") (pintype "output"))
      (node (ref "GATE73") (pin "A") (pinfunction "A_A") (pintype "input"))
    )
    (net (code "149") (name "Net-(GATE72-PadQ)") (class "Default")
      (node (ref "GATE72") (pin "Q") (pinfunction "Q_Q") (pintype "output"))
      (node (ref "GATE75") (pin "B") (pinfunction "B_B") (pintype "input"))
      (node (ref "GATE79") (pin "A") (pinfunction "A_A") (pintype "input"))
    )
    (net (code "150") (name "Net-(GATE73-PadQ)") (class "Default")
      (node (ref "GATE73") (pin "Q") (pinfunction "Q_Q") (pintype "output"))
      (node (ref "GATE74") (pin "A") (pinfunction "A_A") (pintype "input"))
    )
    (net (code "151") (name "Net-(GATE75-PadQ)") (class "Default")
      (node (ref "GATE75") (pin "Q") (pinfunction "Q_Q") (pintype "output"))
      (node (ref "GATE76") (pin "A") (pinfunction "A_A") (pintype "input"))
    )
    (net (code "152") (name "Net-(GATE100-PadA)") (class "Default")
      (node (ref "GATE100") (pin "A") (pinfunction "A_A") (pintype "input"))
      (node (ref "GATE103") (pin "C") (pinfunction "C_C") (pintype "input"))
      (node (ref "GATE125") (pin "C") (pinfunction "C_C") (pintype "input"))
      (node (ref "GATE127") (pin "B") (pinfunction "B_B") (pintype "input"))
      (node (ref "GATE130") (pin "A") (pinfunction "A_A") (pintype "input"))
      (node (ref "GATE131") (pin "A") (pinfunction "A_A") (pintype "input"))
      (node (ref "GATE132") (pin "B") (pinfunction "B_B") (pintype "input"))
      (node (ref "GATE135") (pin "B") (pinfunction "B_B") (pintype "input"))
      (node (ref "GATE80") (pin "Q") (pinfunction "Q_Q") (pintype "output"))
      (node (ref "GATE84") (pin "B") (pinfunction "B_B") (pintype "input"))
      (node (ref "GATE96") (pin "B") (pinfunction "B_B") (pintype "input"))
      (node (ref "GATE99") (pin "A") (pinfunction "A_A") (pintype "input"))
    )
    (net (code "153") (name "Net-(GATE100-PadB)") (class "Default")
      (node (ref "GATE100") (pin "B") (pinfunction "B_B") (pintype "input"))
      (node (ref "GATE131") (pin "C") (pinfunction "C_C") (pintype "input"))
      (node (ref "GATE89") (pin "Q") (pinfunction "Q_Q") (pintype "output"))
      (node (ref "GATE97") (pin "B") (pinfunction "B_B") (pintype "input"))
    )
    (net (code "154") (name "Net-(GATE100-PadQ)") (class "Default")
      (node (ref "GATE100") (pin "Q") (pinfunction "Q_Q") (pintype "output"))
      (node (ref "GATE106") (pin "D") (pinfunction "D_D") (pintype "input"))
      (node (ref "GATE108") (pin "D") (pinfunction "D_D") (pintype "input"))
      (node (ref "GATE110") (pin "D") (pinfunction "D_D") (pintype "input"))
    )
    (net (code "155") (name "Net-(GATE101-PadB)") (class "Default")
      (node (ref "GATE101") (pin "B") (pinfunction "B_B") (pintype "input"))
      (node (ref "GATE102") (pin "B") (pinfunction "B_B") (pintype "input"))
      (node (ref "GATE126") (pin "B") (pinfunction "B_B") (pintype "input"))
      (node (ref "GATE137") (pin "C") (pinfunction "C_C") (pintype "input"))
      (node (ref "GATE138") (pin "C") (pinfunction "C_C") (pintype "input"))
      (node (ref "GATE93") (pin "Q") (pinfunction "Q_Q") (pintype "output"))
      (node (ref "GATE94") (pin "B") (pinfunction "B_B") (pintype "input"))
      (node (ref "GATE95") (pin "C") (pinfunction "C_C") (pintype "input"))
    )
    (net (code "156") (name "Net-(GATE101-PadQ)") (class "Default")
      (node (ref "GATE101") (pin "Q") (pinfunction "Q_Q") (pintype "output"))
      (node (ref "GATE108") (pin "C") (pinfunction "C_C") (pintype "input"))
      (node (ref "GATE110") (pin "C") (pinfunction "C_C") (pintype "input"))
      (node (ref "GATE149") (pin "C") (pinfunction "C_C") (pintype "input"))
      (node (ref "GATE153") (pin "C") (pinfunction "C_C") (pintype "input"))
    )
    (net (code "157") (name "Net-(GATE102-PadA)") (class "Default")
      (node (ref "GATE102") (pin "A") (pinfunction "A_A") (pintype "input"))
      (node (ref "GATE124") (pin "A") (pinfunction "A_A") (pintype "input"))
      (node (ref "GATE127") (pin "C") (pinfunction "C_C") (pintype "input"))
      (node (ref "GATE128") (pin "A") (pinfunction "A_A") (pintype "input"))
      (node (ref "GATE131") (pin "B") (pinfunction "B_B") (pintype "input"))
      (node (ref "GATE134") (pin "B") (pinfunction "B_B") (pintype "input"))
      (node (ref "GATE137") (pin "A") (pinfunction "A_A") (pintype "input"))
      (node (ref "GATE81") (pin "Q") (pinfunction "Q_Q") (pintype "output"))
      (node (ref "GATE87") (pin "B") (pinfunction "B_B") (pintype "input"))
      (node (ref "GATE95") (pin "B") (pinfunction "B_B") (pintype "input"))
      (node (ref "GATE96") (pin "C") (pinfunction "C_C") (pintype "input"))
    )
    (net (code "158") (name "Net-(GATE102-PadQ)") (class "Default")
      (node (ref "GATE102") (pin "Q") (pinfunction "Q_Q") (pintype "output"))
      (node (ref "GATE112") (pin "C") (pinfunction "C_C") (pintype "input"))
      (node (ref "GATE114") (pin "C") (pinfunction "C_C") (pintype "input"))
      (node (ref "GATE116") (pin "B") (pinfunction "B_B") (pintype "input"))
      (node (ref "GATE141") (pin "D") (pinfunction "D_D") (pintype "input"))
      (node (ref "GATE143") (pin "C") (pinfunction "C_C") (pintype "input"))
    )
    (net (code "159") (name "Net-(GATE104-PadA)") (class "Default")
      (node (ref "GATE104") (pin "A") (pinfunction "A_A") (pintype "input"))
      (node (ref "GATE151") (pin "A") (pinfunction "A_A") (pintype "input"))
      (node (ref "GATE84") (pin "Q") (pinfunction "Q_Q") (pintype "output"))
    )
    (net (code "160") (name "Net-(GATE104-PadB)") (class "Default")
      (node (ref "GATE104") (pin "B") (pinfunction "B_B") (pintype "input"))
      (node (ref "GATE151") (pin "C") (pinfunction "C_C") (pintype "input"))
      (node (ref "GATE97") (pin "Q") (pinfunction "Q_Q") (pintype "output"))
    )
    (net (code "161") (name "Net-(GATE104-PadC)") (class "Default")
      (node (ref "GATE104") (pin "C") (pinfunction "C_C") (pintype "input"))
      (node (ref "GATE114") (pin "E") (pinfunction "E_E") (pintype "input"))
      (node (ref "GATE120") (pin "C") (pinfunction "C_C") (pintype "input"))
      (node (ref "GATE122") (pin "B") (pinfunction "B_B") (pintype "input"))
      (node (ref "GATE151") (pin "D") (pinfunction "D_D") (pintype "input"))
      (node (ref "GATE165") (pin "D") (pinfunction "D_D") (pintype "input"))
      (node (ref "GATE96") (pin "Q") (pinfunction "Q_Q") (pintype "output"))
    )
    (net (code "162") (name "Net-(GATE104-PadQ)") (class "Default")
      (node (ref "GATE104") (pin "Q") (pinfunction "Q_Q") (pintype "output"))
      (node (ref "GATE105") (pin "A") (pinfunction "A_A") (pintype "input"))
    )
    (net (code "163") (name "Net-(GATE106-PadA)") (class "Default")
      (node (ref "GATE106") (pin "A") (pinfunction "A_A") (pintype "input"))
      (node (ref "GATE108") (pin "A") (pinfunction "A_A") (pintype "input"))
      (node (ref "GATE141") (pin "A") (pinfunction "A_A") (pintype "input"))
      (node (ref "GATE143") (pin "A") (pinfunction "A_A") (pintype "input"))
      (node (ref "GATE85") (pin "Q") (pinfunction "Q_Q") (pintype "output"))
      (node (ref "GATE86") (pin "A") (pinfunction "A_A") (pintype "input"))
    )
    (net (code "164") (name "Net-(GATE106-PadB)") (class "Default")
      (node (ref "GATE106") (pin "B") (pinfunction "B_B") (pintype "input"))
      (node (ref "GATE108") (pin "B") (pinfunction "B_B") (pintype "input"))
      (node (ref "GATE159") (pin "A") (pinfunction "A_A") (pintype "input"))
      (node (ref "GATE87") (pin "Q") (pinfunction "Q_Q") (pintype "output"))
    )
    (net (code "165") (name "Net-(GATE106-PadC)") (class "Default")
      (node (ref "GATE106") (pin "C") (pinfunction "C_C") (pintype "input"))
      (node (ref "GATE139") (pin "B") (pinfunction "B_B") (pintype "input"))
      (node (ref "GATE149") (pin "D") (pinfunction "D_D") (pintype "input"))
      (node (ref "GATE161") (pin "B") (pinfunction "B_B") (pintype "input"))
      (node (ref "GATE98") (pin "Q") (pinfunction "Q_Q") (pintype "output"))
    )
    (net (code "166") (name "Net-(GATE106-PadQ)") (class "Default")
      (node (ref "GATE106") (pin "Q") (pinfunction "Q_Q") (pintype "output"))
      (node (ref "GATE107") (pin "A") (pinfunction "A_A") (pintype "input"))
    )
    (net (code "167") (name "Net-(GATE108-PadQ)") (class "Default")
      (node (ref "GATE108") (pin "Q") (pinfunction "Q_Q") (pintype "output"))
      (node (ref "GATE109") (pin "A") (pinfunction "A_A") (pintype "input"))
    )
    (net (code "168") (name "Net-(GATE110-PadA)") (class "Default")
      (node (ref "GATE110") (pin "A") (pinfunction "A_A") (pintype "input"))
      (node (ref "GATE135") (pin "Q") (pinfunction "Q_Q") (pintype "output"))
      (node (ref "GATE167") (pin "A") (pinfunction "A_A") (pintype "input"))
    )
    (net (code "169") (name "Net-(GATE110-PadB)") (class "Default")
      (node (ref "GATE110") (pin "B") (pinfunction "B_B") (pintype "input"))
      (node (ref "GATE134") (pin "Q") (pinfunction "Q_Q") (pintype "output"))
    )
    (net (code "170") (name "Net-(GATE110-PadQ)") (class "Default")
      (node (ref "GATE110") (pin "Q") (pinfunction "Q_Q") (pintype "output"))
      (node (ref "GATE111") (pin "A") (pinfunction "A_A") (pintype "input"))
    )
    (net (code "171") (name "Net-(GATE112-PadA)") (class "Default")
      (node (ref "GATE112") (pin "A") (pinfunction "A_A") (pintype "input"))
      (node (ref "GATE137") (pin "B") (pinfunction "B_B") (pintype "input"))
      (node (ref "GATE138") (pin "B") (pinfunction "B_B") (pintype "input"))
      (node (ref "GATE147") (pin "B") (pinfunction "B_B") (pintype "input"))
      (node (ref "GATE83") (pin "Q") (pinfunction "Q_Q") (pintype "output"))
      (node (ref "GATE88") (pin "B") (pinfunction "B_B") (pintype "input"))
      (node (ref "GATE94") (pin "A") (pinfunction "A_A") (pintype "input"))
    )
    (net (code "172") (name "Net-(GATE112-PadQ)") (class "Default")
      (node (ref "GATE112") (pin "Q") (pinfunction "Q_Q") (pintype "output"))
      (node (ref "GATE113") (pin "A") (pinfunction "A_A") (pintype "input"))
    )
    (net (code "173") (name "Net-(GATE114-PadA)") (class "Default")
      (node (ref "GATE114") (pin "A") (pinfunction "A_A") (pintype "input"))
      (node (ref "GATE116") (pin "A") (pinfunction "A_A") (pintype "input"))
      (node (ref "GATE118") (pin "A") (pinfunction "A_A") (pintype "input"))
      (node (ref "GATE136") (pin "Q") (pinfunction "Q_Q") (pintype "output"))
      (node (ref "GATE163") (pin "B") (pinfunction "B_B") (pintype "input"))
      (node (ref "GATE169") (pin "A") (pinfunction "A_A") (pintype "input"))
    )
    (net (code "174") (name "Net-(GATE114-PadD)") (class "Default")
      (node (ref "GATE114") (pin "D") (pinfunction "D_D") (pintype "input"))
      (node (ref "GATE120") (pin "B") (pinfunction "B_B") (pintype "input"))
      (node (ref "GATE122") (pin "A") (pinfunction "A_A") (pintype "input"))
      (node (ref "GATE165") (pin "C") (pinfunction "C_C") (pintype "input"))
      (node (ref "GATE99") (pin "Q") (pinfunction "Q_Q") (pintype "output"))
    )
    (net (code "175") (name "Net-(GATE114-PadQ)") (class "Default")
      (node (ref "GATE114") (pin "Q") (pinfunction "Q_Q") (pintype "output"))
      (node (ref "GATE115") (pin "A") (pinfunction "A_A") (pintype "input"))
    )
    (net (code "176") (name "Net-(GATE116-PadC)") (class "Default")
      (node (ref "GATE116") (pin "C") (pinfunction "C_C") (pintype "input"))
      (node (ref "GATE94") (pin "Q") (pinfunction "Q_Q") (pintype "output"))
    )
    (net (code "177") (name "Net-(GATE116-PadQ)") (class "Default")
      (node (ref "GATE116") (pin "Q") (pinfunction "Q_Q") (pintype "output"))
      (node (ref "GATE117") (pin "A") (pinfunction "A_A") (pintype "input"))
    )
    (net (code "178") (name "Net-(GATE118-PadB)") (class "Default")
      (node (ref "GATE118") (pin "B") (pinfunction "B_B") (pintype "input"))
      (node (ref "GATE95") (pin "Q") (pinfunction "Q_Q") (pintype "output"))
    )
    (net (code "179") (name "Net-(GATE118-PadQ)") (class "Default")
      (node (ref "GATE118") (pin "Q") (pinfunction "Q_Q") (pintype "output"))
      (node (ref "GATE119") (pin "A") (pinfunction "A_A") (pintype "input"))
    )
    (net (code "180") (name "Net-(GATE120-PadA)") (class "Default")
      (node (ref "GATE120") (pin "A") (pinfunction "A_A") (pintype "input"))
      (node (ref "GATE138") (pin "Q") (pinfunction "Q_Q") (pintype "output"))
      (node (ref "GATE165") (pin "A") (pinfunction "A_A") (pintype "input"))
      (node (ref "GATE171") (pin "B") (pinfunction "B_B") (pintype "input"))
    )
    (net (code "181") (name "Net-(GATE120-PadQ)") (class "Default")
      (node (ref "GATE120") (pin "Q") (pinfunction "Q_Q") (pintype "output"))
      (node (ref "GATE121") (pin "A") (pinfunction "A_A") (pintype "input"))
    )
    (net (code "182") (name "Net-(GATE122-PadQ)") (class "Default")
      (node (ref "GATE122") (pin "Q") (pinfunction "Q_Q") (pintype "output"))
      (node (ref "GATE123") (pin "A") (pinfunction "A_A") (pintype "input"))
    )
    (net (code "183") (name "Net-(GATE124-PadB)") (class "Default")
      (node (ref "GATE124") (pin "B") (pinfunction "B_B") (pintype "input"))
      (node (ref "GATE130") (pin "B") (pinfunction "B_B") (pintype "input"))
      (node (ref "GATE133") (pin "B") (pinfunction "B_B") (pintype "input"))
      (node (ref "GATE134") (pin "C") (pinfunction "C_C") (pintype "input"))
      (node (ref "GATE135") (pin "C") (pinfunction "C_C") (pintype "input"))
      (node (ref "GATE136") (pin "C") (pinfunction "C_C") (pintype "input"))
      (node (ref "GATE86") (pin "Q") (pinfunction "Q_Q") (pintype "output"))
    )
    (net (code "184") (name "Net-(GATE124-PadQ)") (class "Default")
      (node (ref "GATE124") (pin "Q") (pinfunction "Q_Q") (pintype "output"))
      (node (ref "GATE145") (pin "C") (pinfunction "C_C") (pintype "input"))
      (node (ref "GATE157") (pin "C") (pinfunction "C_C") (pintype "input"))
      (node (ref "GATE159") (pin "D") (pinfunction "D_D") (pintype "input"))
    )
    (net (code "185") (name "Net-(GATE125-PadQ)") (class "Default")
      (node (ref "GATE125") (pin "Q") (pinfunction "Q_Q") (pintype "output"))
      (node (ref "GATE145") (pin "B") (pinfunction "B_B") (pintype "input"))
      (node (ref "GATE153") (pin "B") (pinfunction "B_B") (pintype "input"))
    )
    (net (code "186") (name "Net-(GATE126-PadQ)") (class "Default")
      (node (ref "GATE126") (pin "Q") (pinfunction "Q_Q") (pintype "output"))
      (node (ref "GATE141") (pin "C") (pinfunction "C_C") (pintype "input"))
      (node (ref "GATE143") (pin "B") (pinfunction "B_B") (pintype "input"))
      (node (ref "GATE167") (pin "C") (pinfunction "C_C") (pintype "input"))
    )
    (net (code "187") (name "Net-(GATE127-PadQ)") (class "Default")
      (node (ref "GATE127") (pin "Q") (pinfunction "Q_Q") (pintype "output"))
      (node (ref "GATE149") (pin "B") (pinfunction "B_B") (pintype "input"))
    )
    (net (code "188") (name "Net-(GATE128-PadB)") (class "Default")
      (node (ref "GATE128") (pin "B") (pinfunction "B_B") (pintype "input"))
      (node (ref "GATE129") (pin "B") (pinfunction "B_B") (pintype "input"))
      (node (ref "GATE132") (pin "C") (pinfunction "C_C") (pintype "input"))
      (node (ref "GATE91") (pin "Q") (pinfunction "Q_Q") (pintype "output"))
      (node (ref "GATE99") (pin "B") (pinfunction "B_B") (pintype "input"))
    )
    (net (code "189") (name "Net-(GATE128-PadQ)") (class "Default")
      (node (ref "GATE128") (pin "Q") (pinfunction "Q_Q") (pintype "output"))
      (node (ref "GATE141") (pin "B") (pinfunction "B_B") (pintype "input"))
      (node (ref "GATE151") (pin "B") (pinfunction "B_B") (pintype "input"))
      (node (ref "GATE165") (pin "B") (pinfunction "B_B") (pintype "input"))
      (node (ref "GATE167") (pin "B") (pinfunction "B_B") (pintype "input"))
      (node (ref "GATE171") (pin "A") (pinfunction "A_A") (pintype "input"))
    )
    (net (code "190") (name "Net-(GATE129-PadQ)") (class "Default")
      (node (ref "GATE129") (pin "Q") (pinfunction "Q_Q") (pintype "output"))
      (node (ref "GATE155") (pin "B") (pinfunction "B_B") (pintype "input"))
    )
    (net (code "191") (name "Net-(GATE130-PadQ)") (class "Default")
      (node (ref "GATE130") (pin "Q") (pinfunction "Q_Q") (pintype "output"))
      (node (ref "GATE155") (pin "A") (pinfunction "A_A") (pintype "input"))
      (node (ref "GATE159") (pin "C") (pinfunction "C_C") (pintype "input"))
    )
    (net (code "192") (name "Net-(GATE132-PadQ)") (class "Default")
      (node (ref "GATE132") (pin "Q") (pinfunction "Q_Q") (pintype "output"))
      (node (ref "GATE157") (pin "A") (pinfunction "A_A") (pintype "input"))
    )
    (net (code "193") (name "Net-(GATE133-PadQ)") (class "Default")
      (node (ref "GATE133") (pin "Q") (pinfunction "Q_Q") (pintype "output"))
      (node (ref "GATE161") (pin "A") (pinfunction "A_A") (pintype "input"))
    )
    (net (code "194") (name "Net-(GATE139-PadA)") (class "Default")
      (node (ref "GATE139") (pin "A") (pinfunction "A_A") (pintype "input"))
      (node (ref "GATE147") (pin "A") (pinfunction "A_A") (pintype "input"))
      (node (ref "GATE82") (pin "Q") (pinfunction "Q_Q") (pintype "output"))
      (node (ref "GATE85") (pin "B") (pinfunction "B_B") (pintype "input"))
    )
    (net (code "195") (name "Net-(GATE139-PadQ)") (class "Default")
      (node (ref "GATE139") (pin "Q") (pinfunction "Q_Q") (pintype "output"))
      (node (ref "GATE140") (pin "A") (pinfunction "A_A") (pintype "input"))
    )
    (net (code "196") (name "Net-(GATE141-PadQ)") (class "Default")
      (node (ref "GATE141") (pin "Q") (pinfunction "Q_Q") (pintype "output"))
      (node (ref "GATE142") (pin "A") (pinfunction "A_A") (pintype "input"))
    )
    (net (code "197") (name "Net-(GATE143-PadQ)") (class "Default")
      (node (ref "GATE143") (pin "Q") (pinfunction "Q_Q") (pintype "output"))
      (node (ref "GATE144") (pin "A") (pinfunction "A_A") (pintype "input"))
    )
    (net (code "198") (name "Net-(GATE145-PadA)") (class "Default")
      (node (ref "GATE145") (pin "A") (pinfunction "A_A") (pintype "input"))
      (node (ref "GATE88") (pin "Q") (pinfunction "Q_Q") (pintype "output"))
      (node (ref "GATE89") (pin "A") (pinfunction "A_A") (pintype "input"))
    )
    (net (code "199") (name "Net-(GATE145-PadQ)") (class "Default")
      (node (ref "GATE145") (pin "Q") (pinfunction "Q_Q") (pintype "output"))
      (node (ref "GATE146") (pin "A") (pinfunction "A_A") (pintype "input"))
    )
    (net (code "200") (name "Net-(GATE147-PadQ)") (class "Default")
      (node (ref "GATE147") (pin "Q") (pinfunction "Q_Q") (pintype "output"))
      (node (ref "GATE148") (pin "A") (pinfunction "A_A") (pintype "input"))
    )
    (net (code "201") (name "Net-(GATE149-PadA)") (class "Default")
      (node (ref "GATE149") (pin "A") (pinfunction "A_A") (pintype "input"))
      (node (ref "GATE153") (pin "A") (pinfunction "A_A") (pintype "input"))
      (node (ref "GATE90") (pin "Q") (pinfunction "Q_Q") (pintype "output"))
      (node (ref "GATE91") (pin "A") (pinfunction "A_A") (pintype "input"))
    )
    (net (code "202") (name "Net-(GATE149-PadQ)") (class "Default")
      (node (ref "GATE149") (pin "Q") (pinfunction "Q_Q") (pintype "output"))
      (node (ref "GATE150") (pin "A") (pinfunction "A_A") (pintype "input"))
    )
    (net (code "203") (name "Net-(GATE151-PadQ)") (class "Default")
      (node (ref "GATE151") (pin "Q") (pinfunction "Q_Q") (pintype "output"))
      (node (ref "GATE152") (pin "A") (pinfunction "A_A") (pintype "input"))
    )
    (net (code "204") (name "Net-(GATE153-PadQ)") (class "Default")
      (node (ref "GATE153") (pin "Q") (pinfunction "Q_Q") (pintype "output"))
      (node (ref "GATE154") (pin "A") (pinfunction "A_A") (pintype "input"))
    )
    (net (code "205") (name "Net-(GATE155-PadQ)") (class "Default")
      (node (ref "GATE155") (pin "Q") (pinfunction "Q_Q") (pintype "output"))
      (node (ref "GATE156") (pin "A") (pinfunction "A_A") (pintype "input"))
    )
    (net (code "206") (name "Net-(GATE157-PadQ)") (class "Default")
      (node (ref "GATE157") (pin "Q") (pinfunction "Q_Q") (pintype "output"))
      (node (ref "GATE158") (pin "A") (pinfunction "A_A") (pintype "input"))
    )
    (net (code "207") (name "Net-(GATE159-PadB)") (class "Default")
      (node (ref "GATE159") (pin "B") (pinfunction "B_B") (pintype "input"))
      (node (ref "GATE92") (pin "Q") (pinfunction "Q_Q") (pintype "output"))
      (node (ref "GATE93") (pin "A") (pinfunction "A_A") (pintype "input"))
    )
    (net (code "208") (name "Net-(GATE159-PadQ)") (class "Default")
      (node (ref "GATE159") (pin "Q") (pinfunction "Q_Q") (pintype "output"))
      (node (ref "GATE160") (pin "A") (pinfunction "A_A") (pintype "input"))
    )
    (net (code "209") (name "Net-(GATE161-PadQ)") (class "Default")
      (node (ref "GATE161") (pin "Q") (pinfunction "Q_Q") (pintype "output"))
      (node (ref "GATE162") (pin "A") (pinfunction "A_A") (pintype "input"))
    )
    (net (code "210") (name "Net-(GATE163-PadQ)") (class "Default")
      (node (ref "GATE163") (pin "Q") (pinfunction "Q_Q") (pintype "output"))
      (node (ref "GATE164") (pin "A") (pinfunction "A_A") (pintype "input"))
    )
    (net (code "211") (name "Net-(GATE165-PadQ)") (class "Default")
      (node (ref "GATE165") (pin "Q") (pinfunction "Q_Q") (pintype "output"))
      (node (ref "GATE166") (pin "A") (pinfunction "A_A") (pintype "input"))
    )
    (net (code "212") (name "Net-(GATE167-PadQ)") (class "Default")
      (node (ref "GATE167") (pin "Q") (pinfunction "Q_Q") (pintype "output"))
      (node (ref "GATE168") (pin "A") (pinfunction "A_A") (pintype "input"))
    )
    (net (code "213") (name "Net-(GATE169-PadQ)") (class "Default")
      (node (ref "GATE169") (pin "Q") (pinfunction "Q_Q") (pintype "output"))
      (node (ref "GATE170") (pin "A") (pinfunction "A_A") (pintype "input"))
    )
    (net (code "214") (name "Net-(GATE171-PadQ)") (class "Default")
      (node (ref "GATE171") (pin "Q") (pinfunction "Q_Q") (pintype "output"))
      (node (ref "GATE172") (pin "A") (pinfunction "A_A") (pintype "input"))
    )
    (net (code "215") (name "SEC_TENS_SEG_AD") (class "Default")
      (node (ref "D_BUS") (pin "8") (pinfunction "8_8") (pintype "passive"))
    )
    (net (code "216") (name "SEC_TENS_SEG_B") (class "Default")
      (node (ref "D_BUS") (pin "9") (pinfunction "9_9") (pintype "passive"))
    )
    (net (code "217") (name "SEC_TENS_SEG_C") (class "Default")
      (node (ref "D_BUS") (pin "10") (pinfunction "10_10") (pintype "passive"))
    )
    (net (code "218") (name "SEC_TENS_SEG_E") (class "Default")
      (node (ref "D_BUS") (pin "11") (pinfunction "11_11") (pintype "passive"))
    )
    (net (code "219") (name "SEC_TENS_SEG_F") (class "Default")
      (node (ref "D_BUS") (pin "12") (pinfunction "12_12") (pintype "passive"))
    )
    (net (code "220") (name "SEC_TENS_SEG_G") (class "Default")
      (node (ref "D_BUS") (pin "13") (pinfunction "13_13") (pintype "passive"))
    )
    (net (code "221") (name "SEC_UNIT_SEG_A") (class "Default")
      (node (ref "D_BUS") (pin "1") (pinfunction "1_1") (pintype "passive"))
    )
    (net (code "222") (name "SEC_UNIT_SEG_B") (class "Default")
      (node (ref "D_BUS") (pin "2") (pinfunction "2_2") (pintype "passive"))
    )
    (net (code "223") (name "SEC_UNIT_SEG_C") (class "Default")
      (node (ref "D_BUS") (pin "3") (pinfunction "3_3") (pintype "passive"))
    )
    (net (code "224") (name "SEC_UNIT_SEG_D") (class "Default")
      (node (ref "D_BUS") (pin "4") (pinfunction "4_4") (pintype "passive"))
    )
    (net (code "225") (name "SEC_UNIT_SEG_E") (class "Default")
      (node (ref "D_BUS") (pin "5") (pinfunction "5_5") (pintype "passive"))
    )
    (net (code "226") (name "SEC_UNIT_SEG_F") (class "Default")
      (node (ref "D_BUS") (pin "6") (pinfunction "6_6") (pintype "passive"))
    )
    (net (code "227") (name "SEC_UNIT_SEG_G") (class "Default")
      (node (ref "D_BUS") (pin "7") (pinfunction "7_7") (pintype "passive"))
    )
    (net (code "228") (name "VDD") (class "Default")
      (node (ref "A_BUS") (pin "38") (pinfunction "38_38") (pintype "passive"))
      (node (ref "A_BUS") (pin "40") (pinfunction "40_40") (pintype "passive"))
      (node (ref "C1") (pin "+") (pinfunction "+_+") (pintype "passive"))
      (node (ref "R2") (pin "1") (pinfunction "1_1") (pintype "passive"))
    )
    (net (code "229") (name "VSS") (class "Default")
      (node (ref "A_BUS") (pin "37") (pinfunction "37_37") (pintype "passive"))
      (node (ref "A_BUS") (pin "39") (pinfunction "39_39") (pintype "passive"))
      (node (ref "C1") (pin "-") (pinfunction "-_-") (pintype "passive"))
    )
    (net (code "230") (name "unconnected-(A_BUS-Pad1)") (class "Default")
      (node (ref "A_BUS") (pin "1") (pinfunction "1_1") (pintype "passive"))
    )
    (net (code "231") (name "unconnected-(A_BUS-Pad2)") (class "Default")
      (node (ref "A_BUS") (pin "2") (pinfunction "2_2") (pintype "passive"))
    )
    (net (code "232") (name "unconnected-(A_BUS-Pad3)") (class "Default")
      (node (ref "A_BUS") (pin "3") (pinfunction "3_3") (pintype "passive"))
    )
    (net (code "233") (name "unconnected-(A_BUS-Pad4)") (class "Default")
      (node (ref "A_BUS") (pin "4") (pinfunction "4_4") (pintype "passive"))
    )
    (net (code "234") (name "unconnected-(A_BUS-Pad5)") (class "Default")
      (node (ref "A_BUS") (pin "5") (pinfunction "5_5") (pintype "passive"))
    )
    (net (code "235") (name "unconnected-(A_BUS-Pad6)") (class "Default")
      (node (ref "A_BUS") (pin "6") (pinfunction "6_6") (pintype "passive"))
    )
    (net (code "236") (name "unconnected-(A_BUS-Pad7)") (class "Default")
      (node (ref "A_BUS") (pin "7") (pinfunction "7_7") (pintype "passive"))
    )
    (net (code "237") (name "unconnected-(A_BUS-Pad8)") (class "Default")
      (node (ref "A_BUS") (pin "8") (pinfunction "8_8") (pintype "passive"))
    )
    (net (code "238") (name "unconnected-(A_BUS-Pad9)") (class "Default")
      (node (ref "A_BUS") (pin "9") (pinfunction "9_9") (pintype "passive"))
    )
    (net (code "239") (name "unconnected-(A_BUS-Pad10)") (class "Default")
      (node (ref "A_BUS") (pin "10") (pinfunction "10_10") (pintype "passive"))
    )
    (net (code "240") (name "unconnected-(A_BUS-Pad11)") (class "Default")
      (node (ref "A_BUS") (pin "11") (pinfunction "11_11") (pintype "passive"))
    )
    (net (code "241") (name "unconnected-(A_BUS-Pad12)") (class "Default")
      (node (ref "A_BUS") (pin "12") (pinfunction "12_12") (pintype "passive"))
    )
    (net (code "242") (name "unconnected-(A_BUS-Pad13)") (class "Default")
      (node (ref "A_BUS") (pin "13") (pinfunction "13_13") (pintype "passive"))
    )
    (net (code "243") (name "unconnected-(A_BUS-Pad14)") (class "Default")
      (node (ref "A_BUS") (pin "14") (pinfunction "14_14") (pintype "passive"))
    )
    (net (code "244") (name "unconnected-(A_BUS-Pad15)") (class "Default")
      (node (ref "A_BUS") (pin "15") (pinfunction "15_15") (pintype "passive"))
    )
    (net (code "245") (name "unconnected-(A_BUS-Pad16)") (class "Default")
      (node (ref "A_BUS") (pin "16") (pinfunction "16_16") (pintype "passive"))
    )
    (net (code "246") (name "unconnected-(A_BUS-Pad17)") (class "Default")
      (node (ref "A_BUS") (pin "17") (pinfunction "17_17") (pintype "passive"))
    )
    (net (code "247") (name "unconnected-(A_BUS-Pad18)") (class "Default")
      (node (ref "A_BUS") (pin "18") (pinfunction "18_18") (pintype "passive"))
    )
    (net (code "248") (name "unconnected-(A_BUS-Pad19)") (class "Default")
      (node (ref "A_BUS") (pin "19") (pinfunction "19_19") (pintype "passive"))
    )
    (net (code "249") (name "unconnected-(A_BUS-Pad20)") (class "Default")
      (node (ref "A_BUS") (pin "20") (pinfunction "20_20") (pintype "passive"))
    )
    (net (code "250") (name "unconnected-(A_BUS-Pad21)") (class "Default")
      (node (ref "A_BUS") (pin "21") (pinfunction "21_21") (pintype "passive"))
    )
    (net (code "251") (name "unconnected-(A_BUS-Pad22)") (class "Default")
      (node (ref "A_BUS") (pin "22") (pinfunction "22_22") (pintype "passive"))
    )
    (net (code "252") (name "unconnected-(A_BUS-Pad23)") (class "Default")
      (node (ref "A_BUS") (pin "23") (pinfunction "23_23") (pintype "passive"))
    )
    (net (code "253") (name "unconnected-(A_BUS-Pad24)") (class "Default")
      (node (ref "A_BUS") (pin "24") (pinfunction "24_24") (pintype "passive"))
    )
    (net (code "254") (name "unconnected-(A_BUS-Pad25)") (class "Default")
      (node (ref "A_BUS") (pin "25") (pinfunction "25_25") (pintype "passive"))
    )
    (net (code "255") (name "unconnected-(A_BUS-Pad26)") (class "Default")
      (node (ref "A_BUS") (pin "26") (pinfunction "26_26") (pintype "passive"))
    )
    (net (code "256") (name "unconnected-(A_BUS-Pad27)") (class "Default")
      (node (ref "A_BUS") (pin "27") (pinfunction "27_27") (pintype "passive"))
    )
    (net (code "257") (name "unconnected-(A_BUS-Pad28)") (class "Default")
      (node (ref "A_BUS") (pin "28") (pinfunction "28_28") (pintype "passive"))
    )
    (net (code "258") (name "unconnected-(A_BUS-Pad29)") (class "Default")
      (node (ref "A_BUS") (pin "29") (pinfunction "29_29") (pintype "passive"))
    )
    (net (code "259") (name "unconnected-(A_BUS-Pad30)") (class "Default")
      (node (ref "A_BUS") (pin "30") (pinfunction "30_30") (pintype "passive"))
    )
    (net (code "260") (name "unconnected-(A_BUS-Pad31)") (class "Default")
      (node (ref "A_BUS") (pin "31") (pinfunction "31_31") (pintype "passive"))
    )
    (net (code "261") (name "unconnected-(A_BUS-Pad32)") (class "Default")
      (node (ref "A_BUS") (pin "32") (pinfunction "32_32") (pintype "passive"))
    )
    (net (code "262") (name "unconnected-(A_BUS-Pad33)") (class "Default")
      (node (ref "A_BUS") (pin "33") (pinfunction "33_33") (pintype "passive"))
    )
    (net (code "263") (name "unconnected-(A_BUS-Pad34)") (class "Default")
      (node (ref "A_BUS") (pin "34") (pinfunction "34_34") (pintype "passive"))
    )
    (net (code "264") (name "unconnected-(A_BUS-Pad35)") (class "Default")
      (node (ref "A_BUS") (pin "35") (pinfunction "35_35") (pintype "passive"))
    )
    (net (code "265") (name "unconnected-(A_BUS-Pad36)") (class "Default")
      (node (ref "A_BUS") (pin "36") (pinfunction "36_36") (pintype "passive"))
    )
    (net (code "266") (name "unconnected-(C_BUS-Pad36)") (class "Default")
      (node (ref "C_BUS") (pin "36") (pinfunction "36_36") (pintype "passive"))
    )
    (net (code "267") (name "unconnected-(C_BUS-Pad37)") (class "Default")
      (node (ref "C_BUS") (pin "37") (pinfunction "37_37") (pintype "passive"))
    )
    (net (code "268") (name "unconnected-(C_BUS-Pad38)") (class "Default")
      (node (ref "C_BUS") (pin "38") (pinfunction "38_38") (pintype "passive"))
    )
    (net (code "269") (name "unconnected-(C_BUS-Pad39)") (class "Default")
      (node (ref "C_BUS") (pin "39") (pinfunction "39_39") (pintype "passive"))
    )
    (net (code "270") (name "unconnected-(C_BUS-Pad40)") (class "Default")
      (node (ref "C_BUS") (pin "40") (pinfunction "40_40") (pintype "passive"))
    )
    (net (code "271") (name "unconnected-(D_BUS-Pad40)") (class "Default")
      (node (ref "D_BUS") (pin "40") (pinfunction "40_40") (pintype "passive"))
    )
  )
)
